# Potentiostat.net
KiCad netlist of a schematic drawn in EAGLE
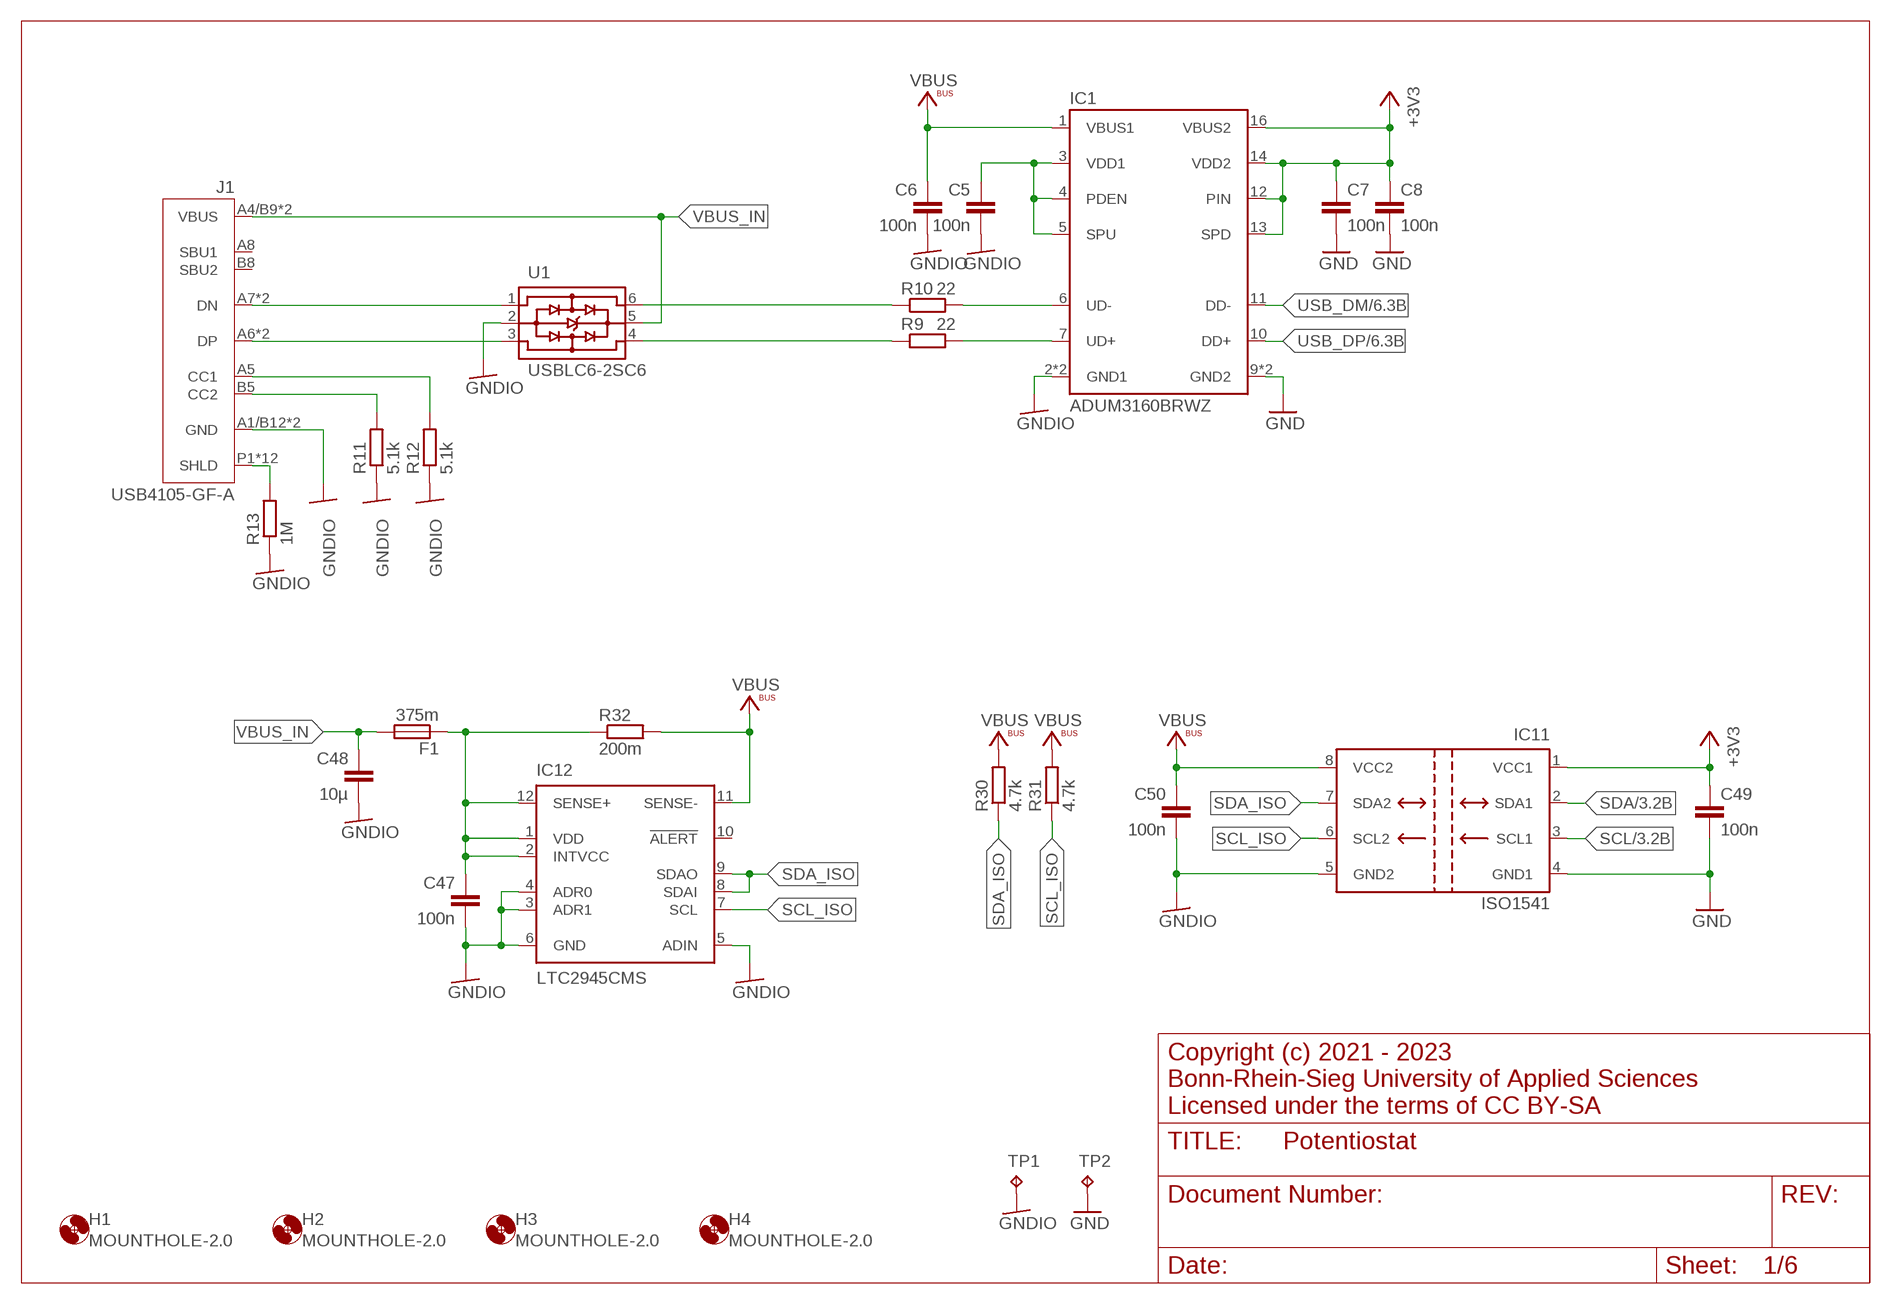
[diagram p0: schematic, sheet 1]
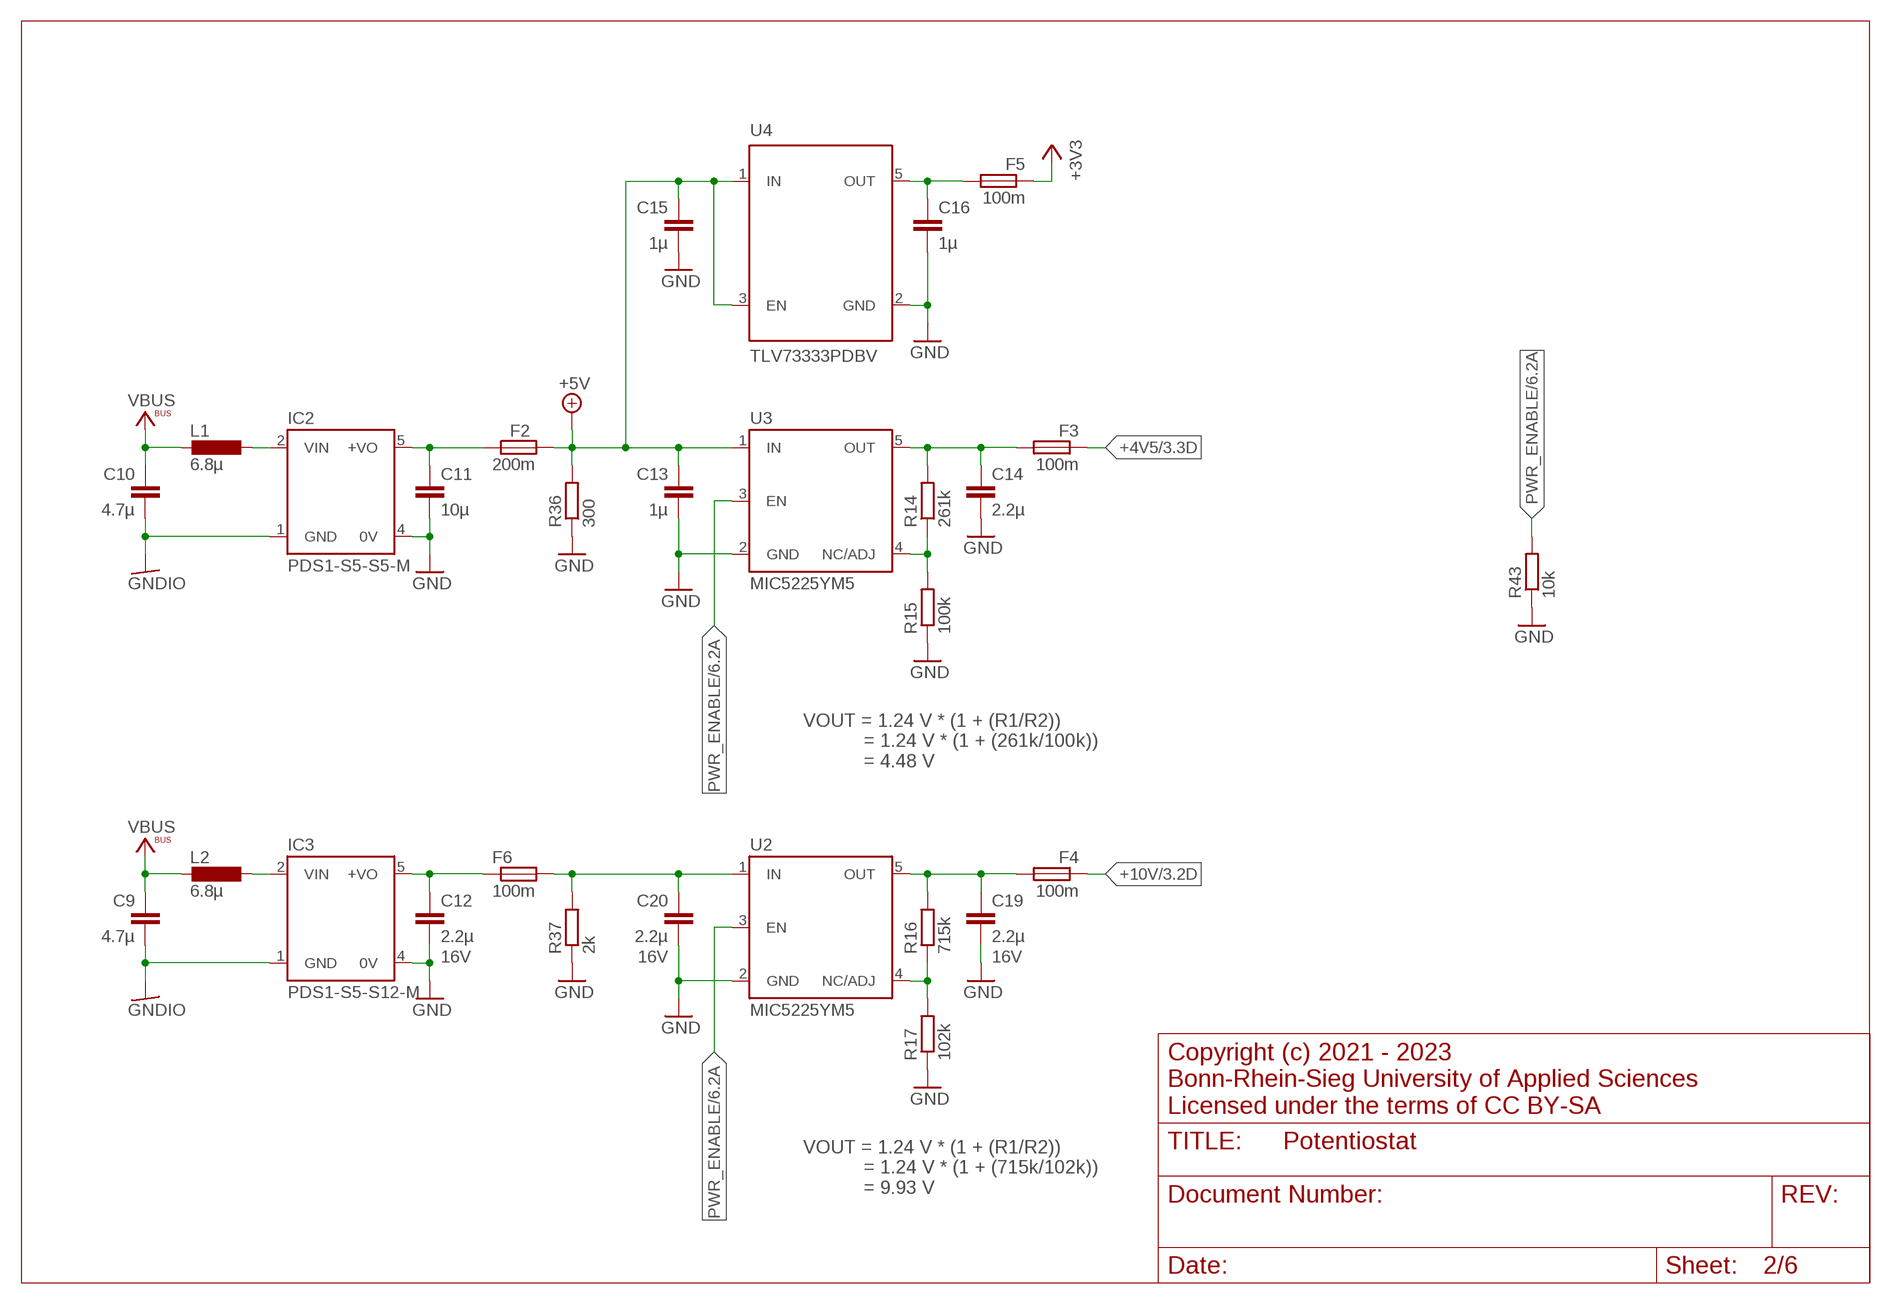
[diagram p1: schematic, sheet 2]
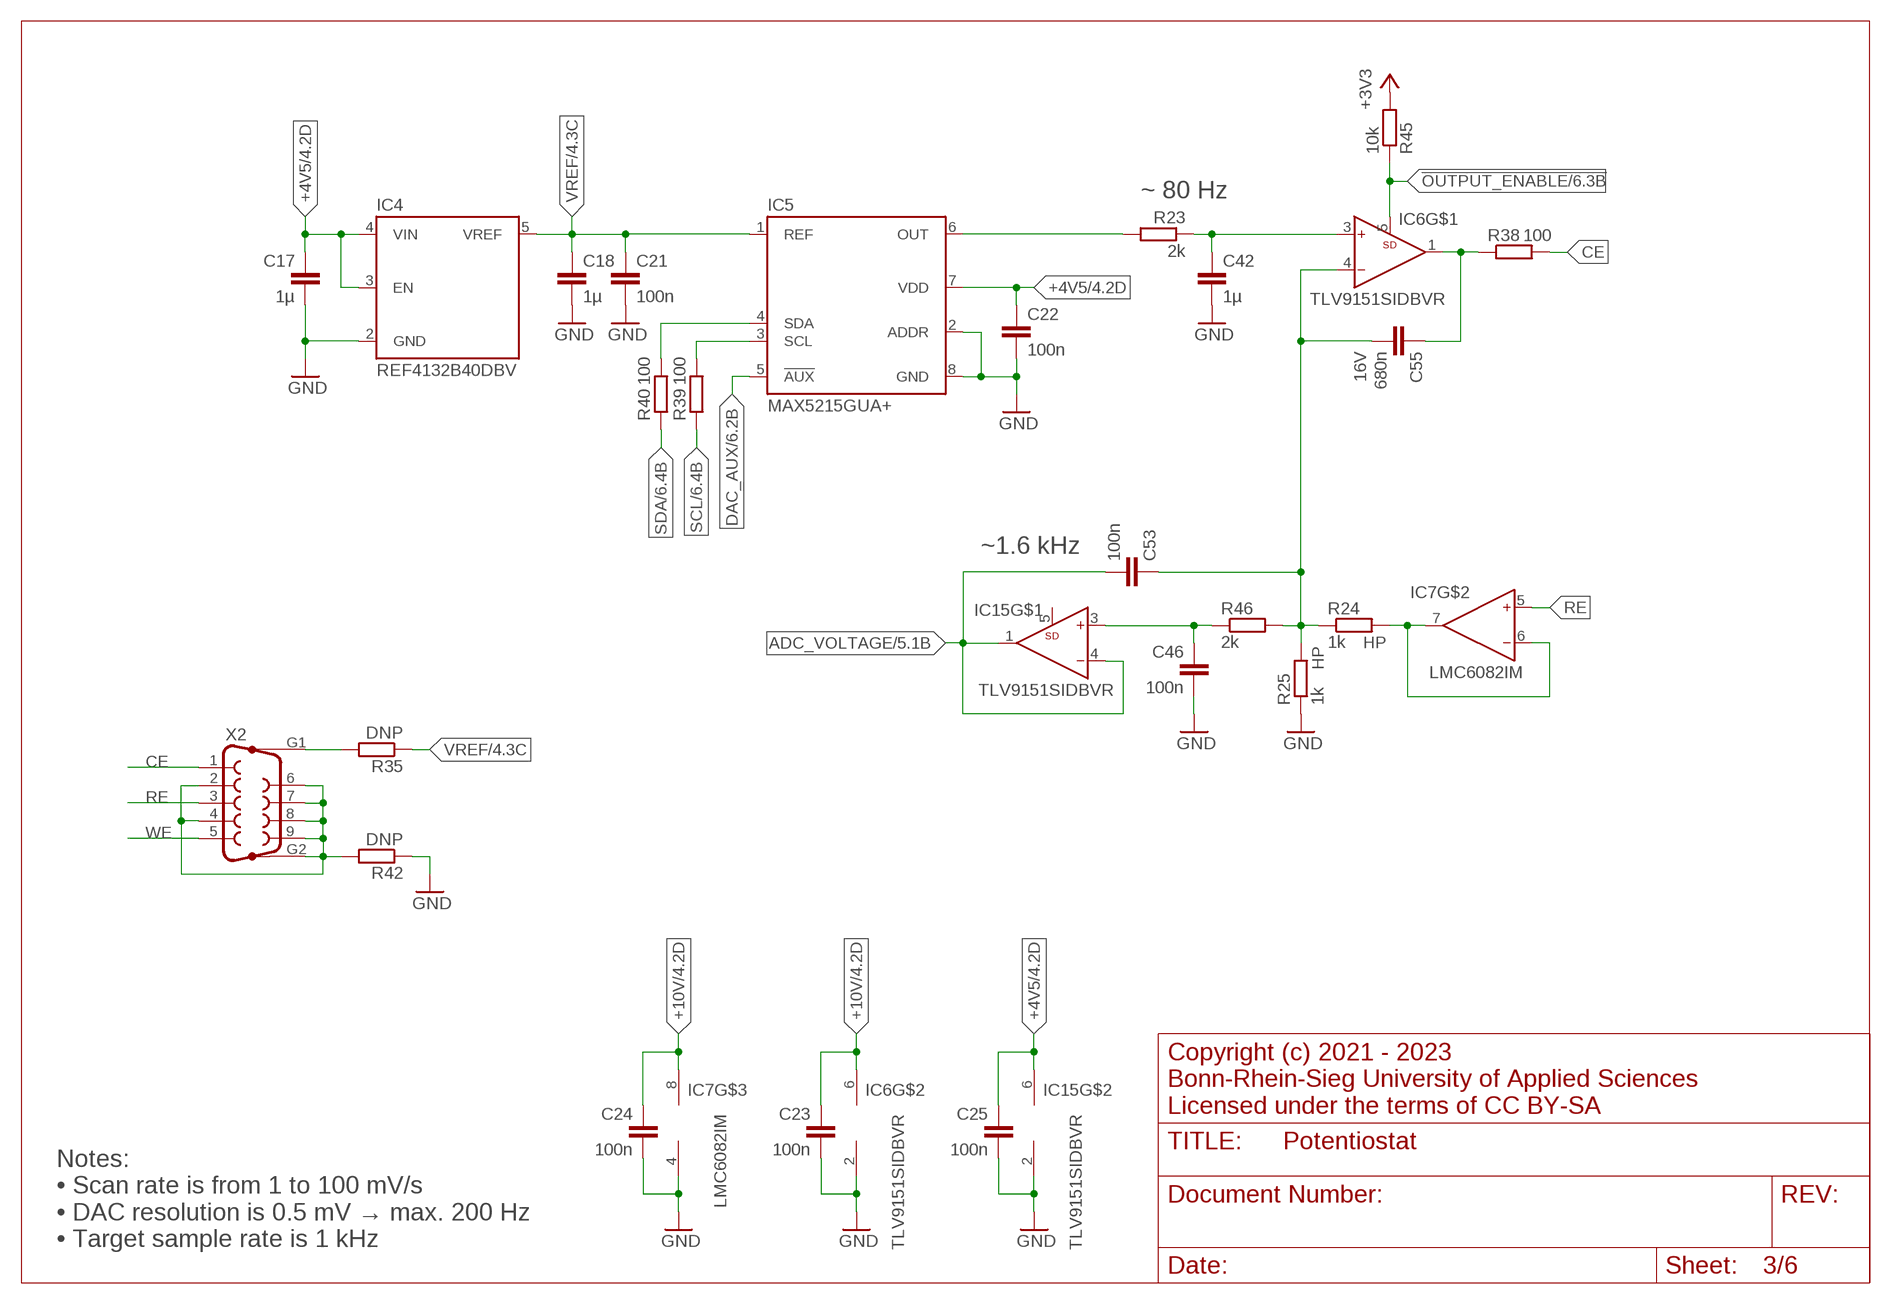
[diagram p2: schematic, sheet 3]
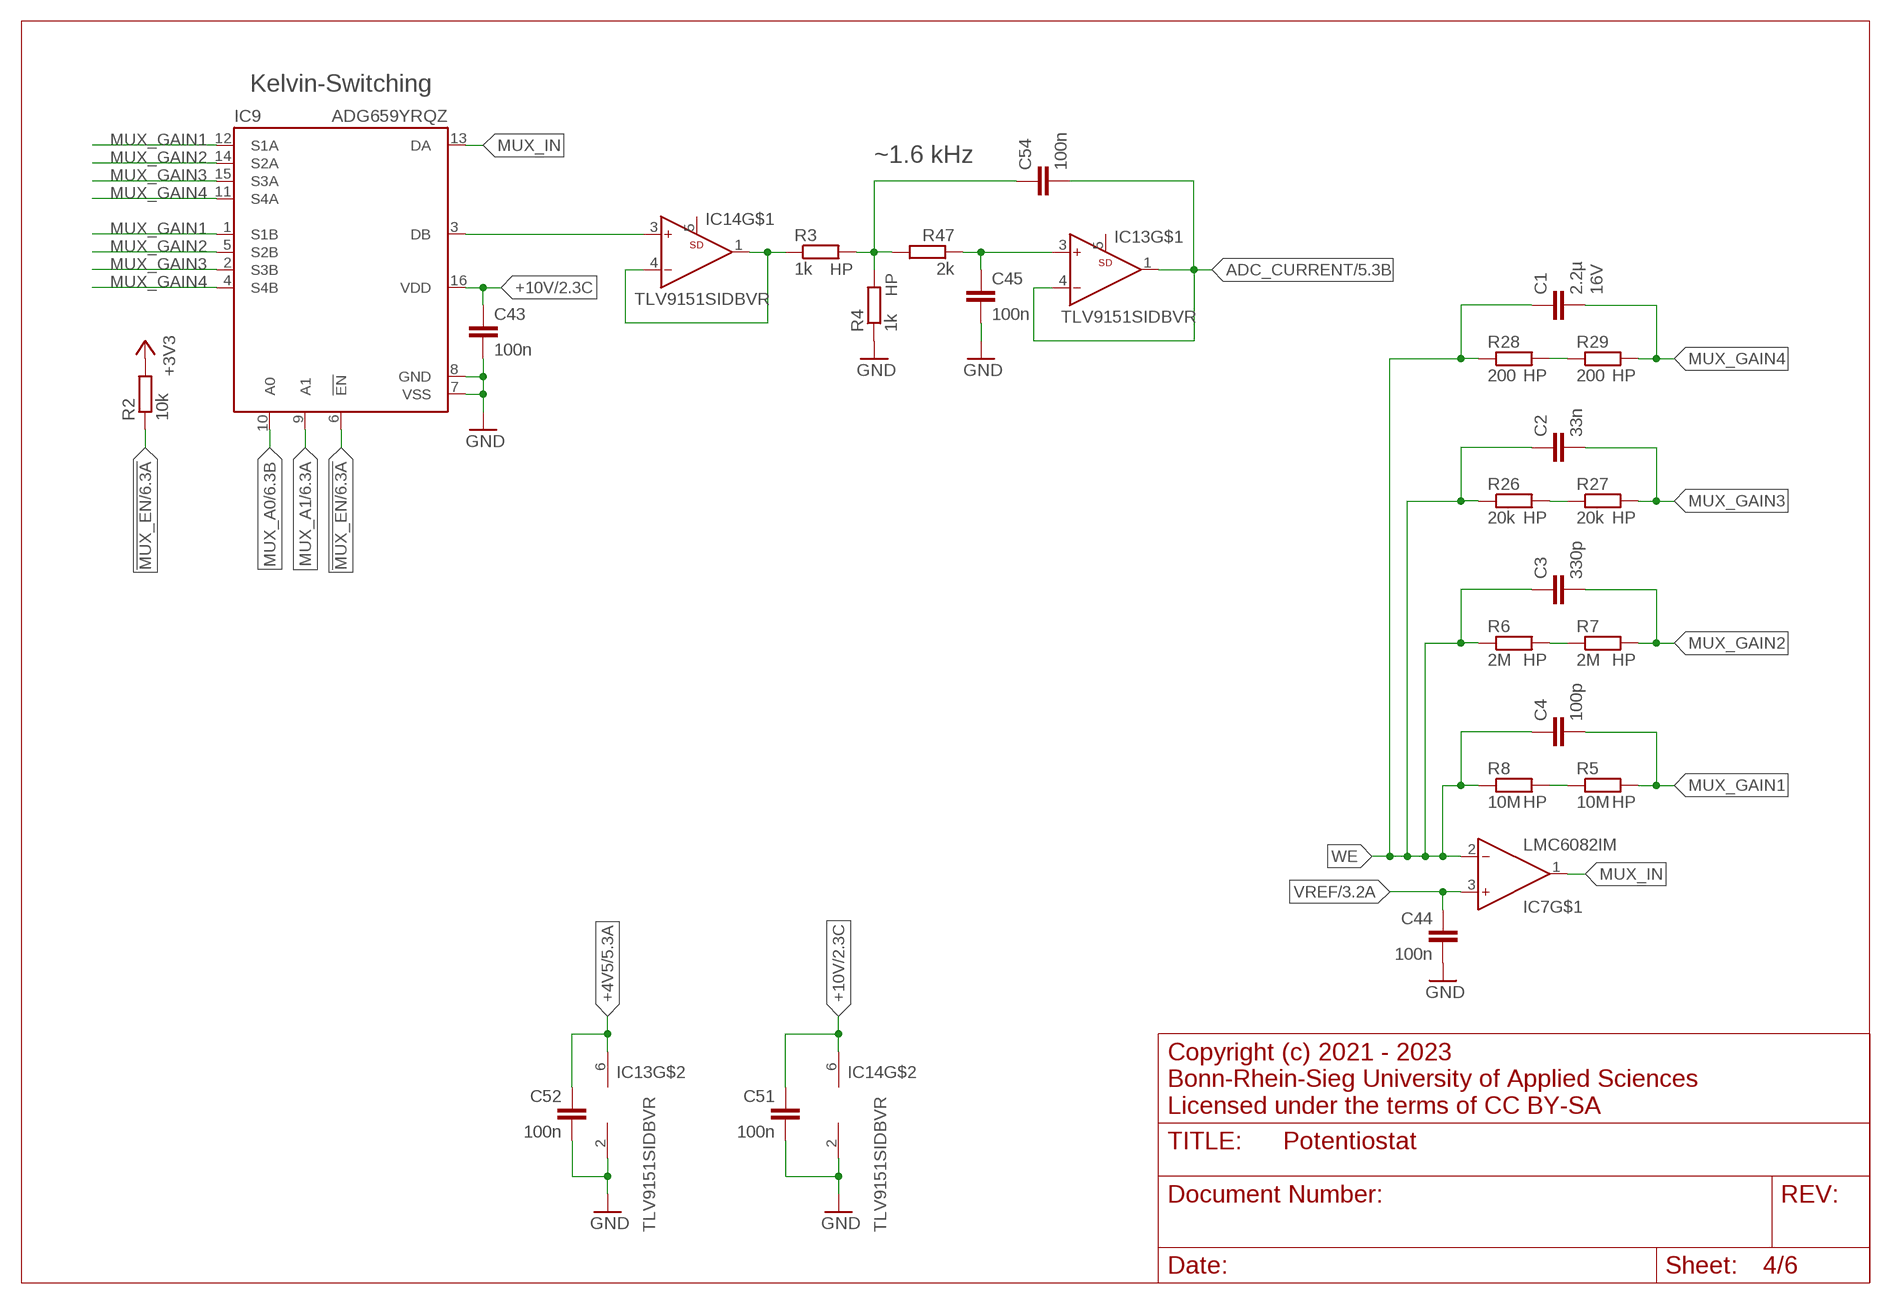
[diagram p3: schematic, sheet 4]
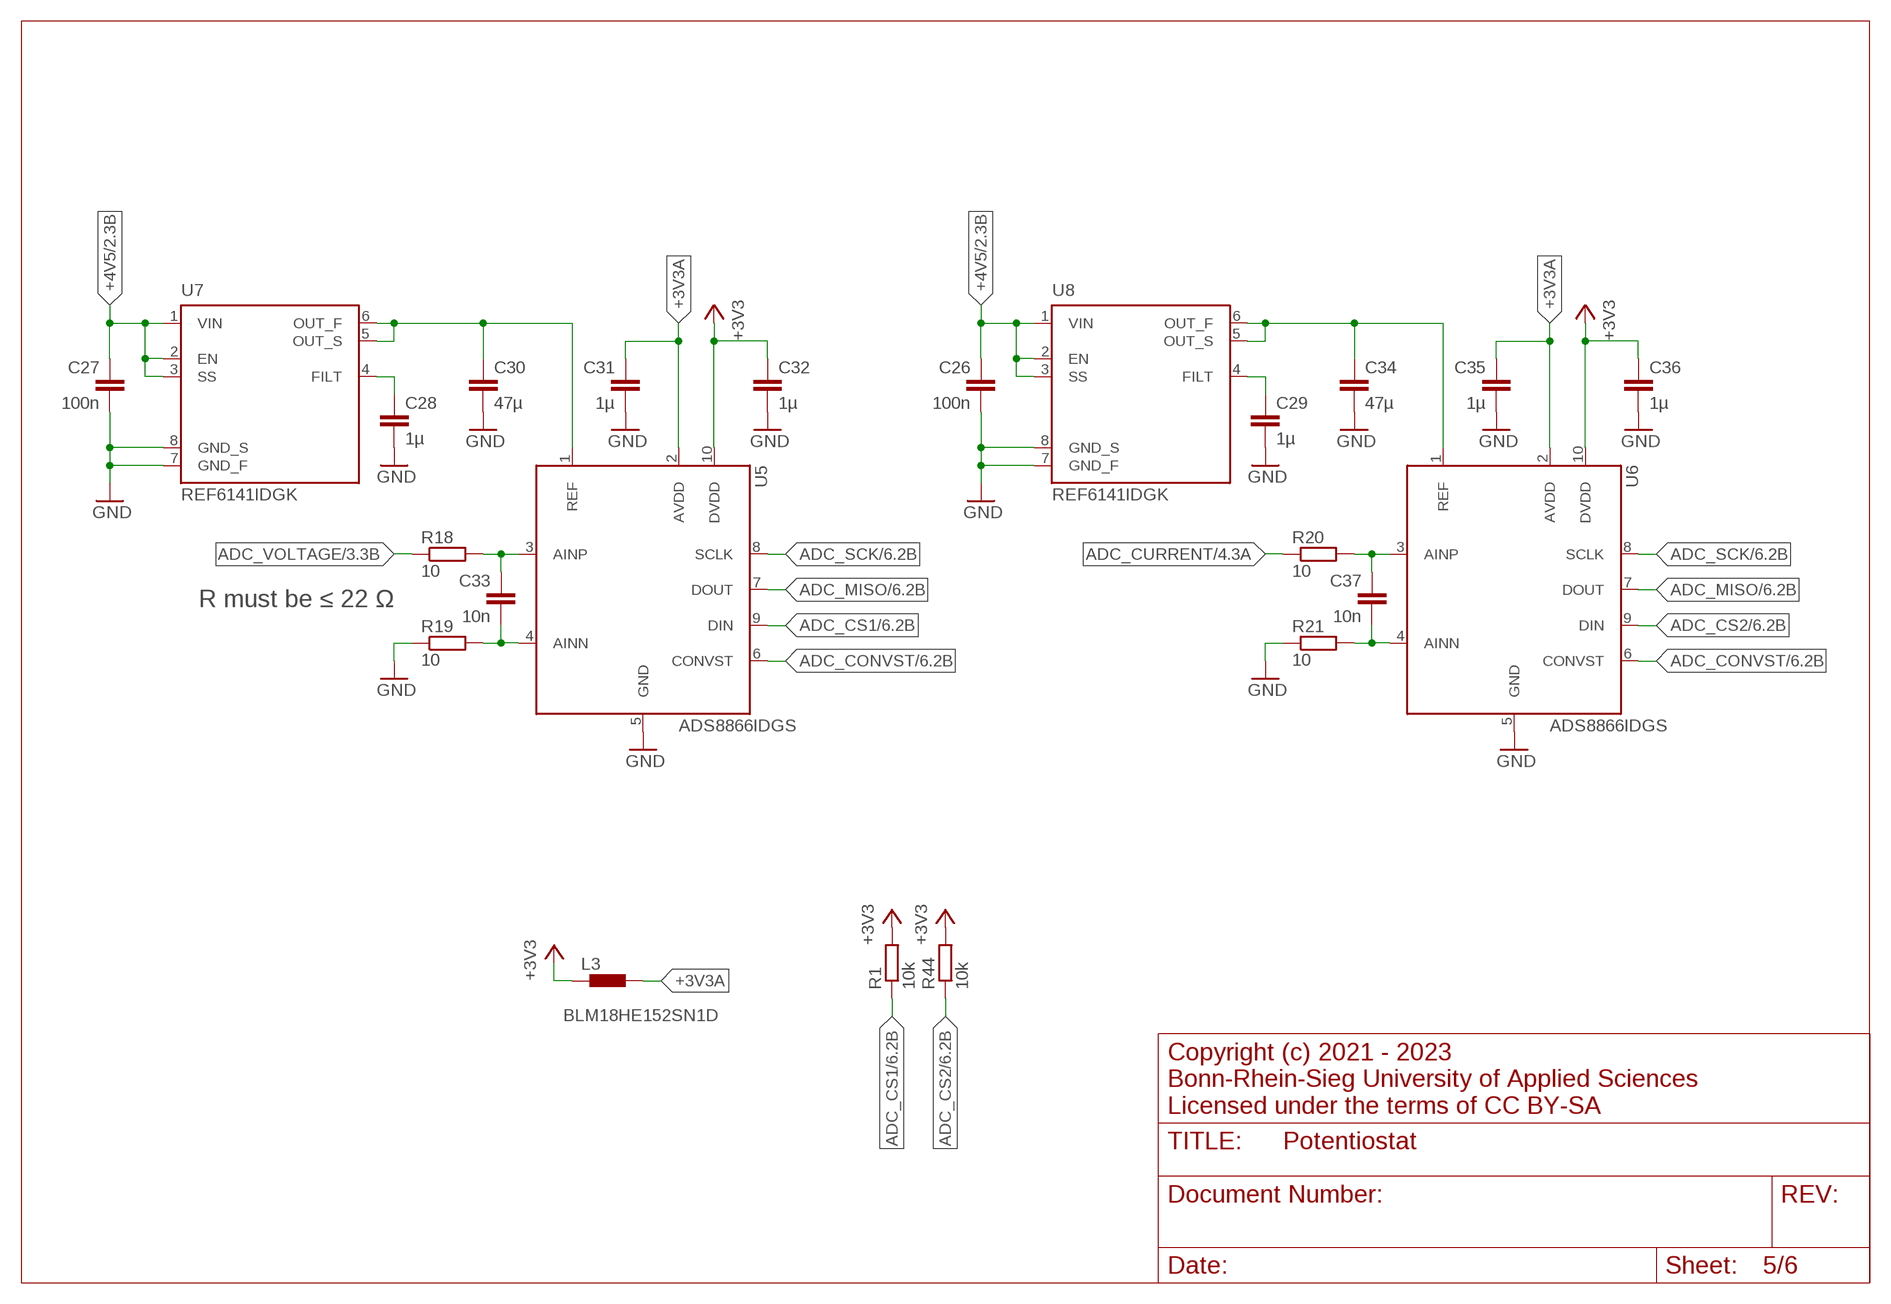
[diagram p4: schematic, sheet 5]
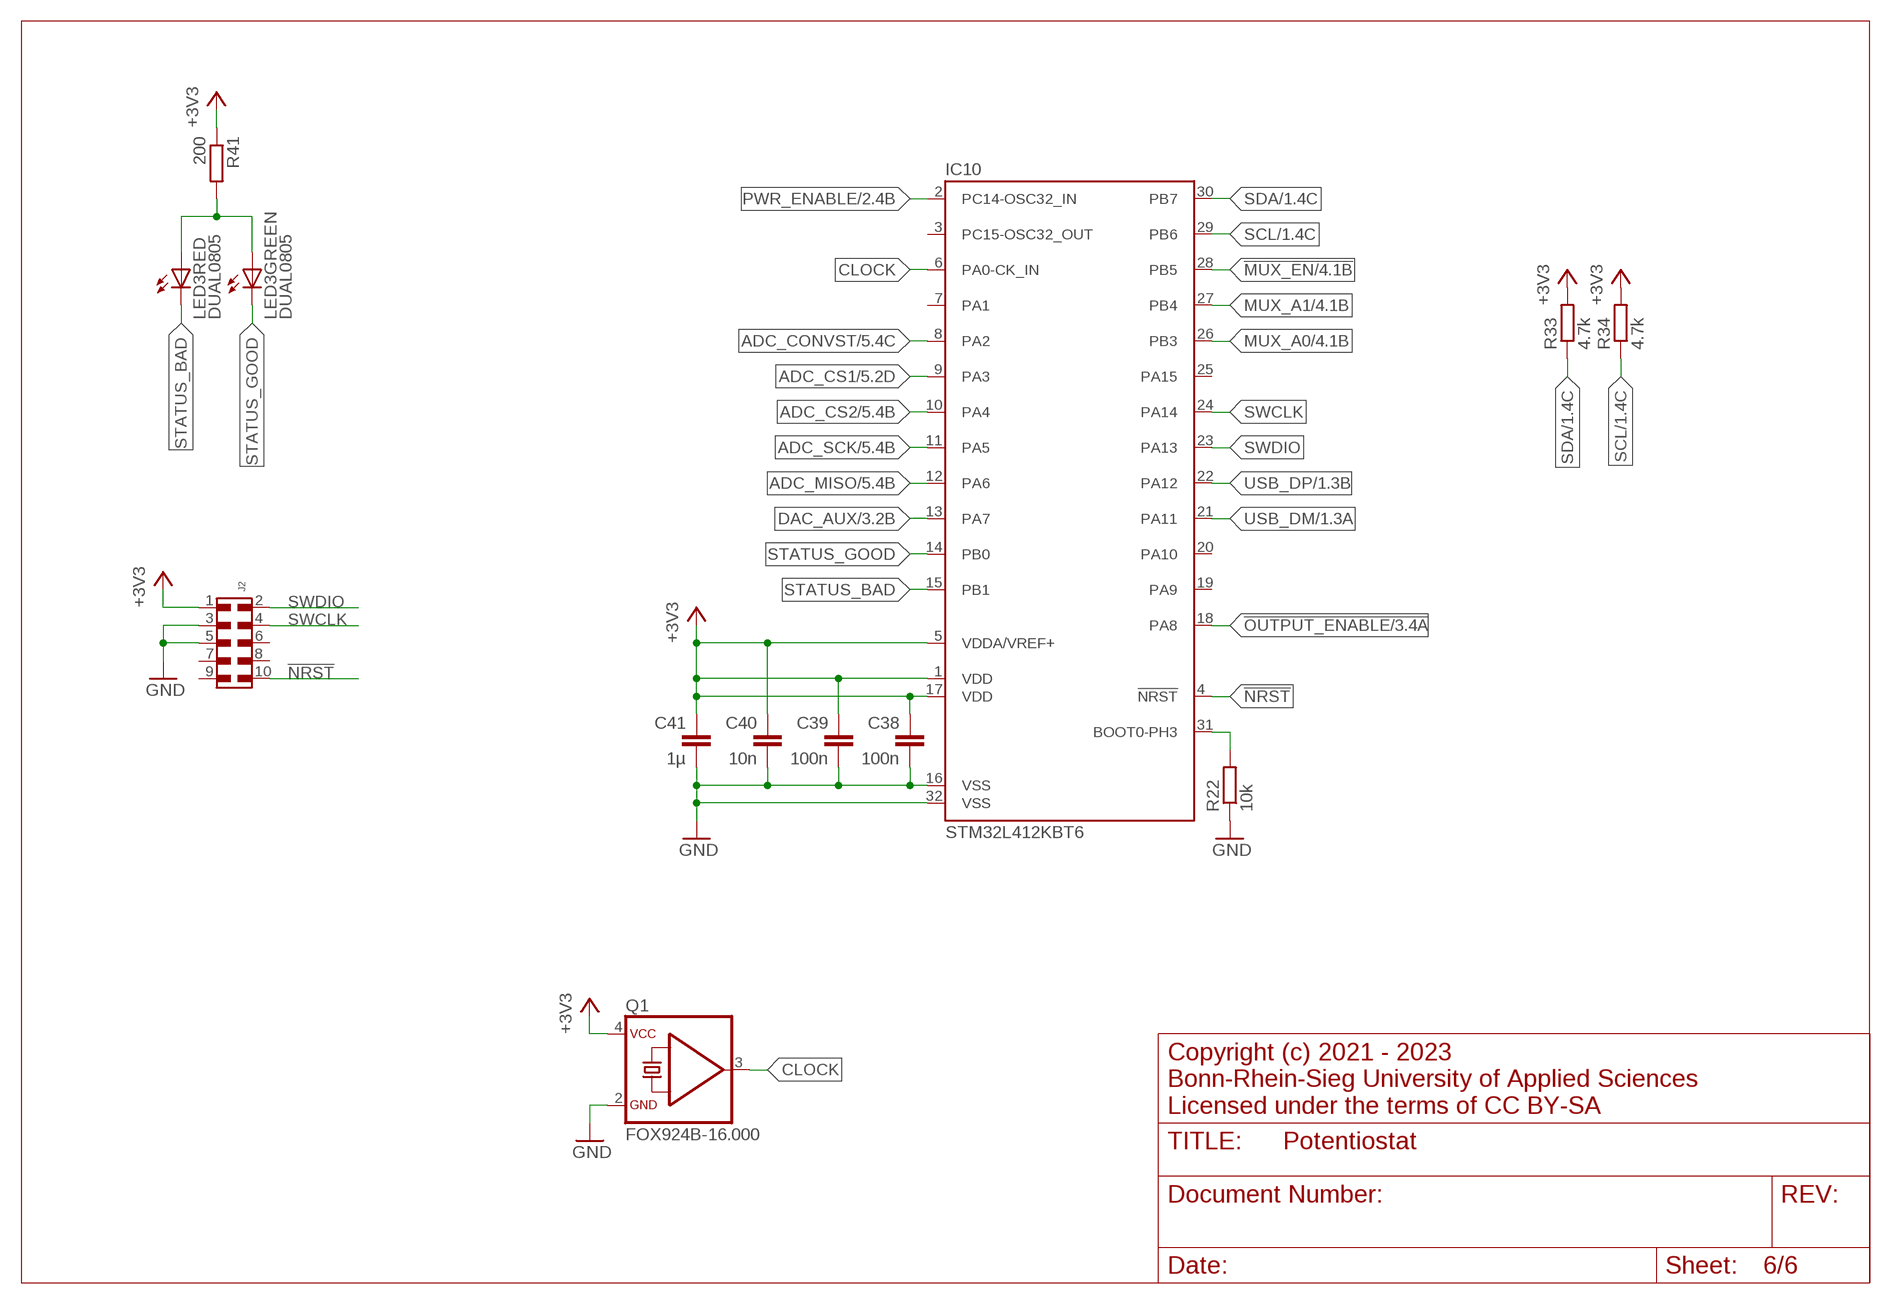
[diagram p5: schematic, sheet 6]

(export (version "E")
  (design (tool "Eeschema 10.0.6"))
  (components
    (comp (ref "C26")
      (value "100n")
      (footprint "eagle-import:C0603")
      (libsource (lib "eagle-import") (part "C-EUC0603"))
    )
    (comp (ref "C27")
      (value "100n")
      (footprint "eagle-import:C0603")
      (libsource (lib "eagle-import") (part "C-EUC0603"))
    )
    (comp (ref "C28")
      (value "1µ")
      (footprint "eagle-import:C0603")
      (libsource (lib "eagle-import") (part "C-EUC0603"))
    )
    (comp (ref "C29")
      (value "1µ")
      (footprint "eagle-import:C0603")
      (libsource (lib "eagle-import") (part "C-EUC0603"))
    )
    (comp (ref "C30")
      (value "47µ")
      (footprint "eagle-import:C0805")
      (libsource (lib "eagle-import") (part "C-EUC0805"))
    )
    (comp (ref "C31")
      (value "1µ")
      (footprint "eagle-import:C0603")
      (libsource (lib "eagle-import") (part "C-EUC0603"))
    )
    (comp (ref "C32")
      (value "1µ")
      (footprint "eagle-import:C0603")
      (libsource (lib "eagle-import") (part "C-EUC0603"))
    )
    (comp (ref "C33")
      (value "10n")
      (footprint "eagle-import:C0603")
      (libsource (lib "eagle-import") (part "C-EUC0603"))
    )
    (comp (ref "C34")
      (value "47µ")
      (footprint "eagle-import:C0805")
      (libsource (lib "eagle-import") (part "C-EUC0805"))
    )
    (comp (ref "C35")
      (value "1µ")
      (footprint "eagle-import:C0603")
      (libsource (lib "eagle-import") (part "C-EUC0603"))
    )
    (comp (ref "C36")
      (value "1µ")
      (footprint "eagle-import:C0603")
      (libsource (lib "eagle-import") (part "C-EUC0603"))
    )
    (comp (ref "C37")
      (value "10n")
      (footprint "eagle-import:C0603")
      (libsource (lib "eagle-import") (part "C-EUC0603"))
    )
    (comp (ref "L3")
      (value "BLM18HE152SN1D")
      (footprint "eagle-import:0603")
      (libsource (lib "eagle-import") (part "BLM18HE152SN1D"))
    )
    (comp (ref "R1")
      (value "10k")
      (footprint "eagle-import:R0603")
      (libsource (lib "eagle-import") (part "R-EU_R0603"))
    )
    (comp (ref "R18")
      (value "10")
      (footprint "eagle-import:R0603")
      (libsource (lib "eagle-import") (part "R-EU_R0603"))
    )
    (comp (ref "R19")
      (value "10")
      (footprint "eagle-import:R0603")
      (libsource (lib "eagle-import") (part "R-EU_R0603"))
    )
    (comp (ref "R20")
      (value "10")
      (footprint "eagle-import:R0603")
      (libsource (lib "eagle-import") (part "R-EU_R0603"))
    )
    (comp (ref "R21")
      (value "10")
      (footprint "eagle-import:R0603")
      (libsource (lib "eagle-import") (part "R-EU_R0603"))
    )
    (comp (ref "R44")
      (value "10k")
      (footprint "eagle-import:R0603")
      (libsource (lib "eagle-import") (part "R-EU_R0603"))
    )
    (comp (ref "U5")
      (value "ADS8866IDGS")
      (footprint "eagle-import:MSOP10")
      (libsource (lib "eagle-import") (part "ADS8866IDGS"))
    )
    (comp (ref "U6")
      (value "ADS8866IDGS")
      (footprint "eagle-import:MSOP10")
      (libsource (lib "eagle-import") (part "ADS8866IDGS"))
    )
    (comp (ref "U7")
      (value "REF6141IDGK")
      (footprint "eagle-import:VSSOP8")
      (libsource (lib "eagle-import") (part "REF61IDGK41"))
    )
    (comp (ref "U8")
      (value "REF6141IDGK")
      (footprint "eagle-import:VSSOP8")
      (libsource (lib "eagle-import") (part "REF61IDGK41"))
    )
    (comp (ref "C17")
      (value "1µ")
      (footprint "eagle-import:C0603")
      (libsource (lib "eagle-import") (part "C-EUC0603"))
    )
    (comp (ref "C18")
      (value "1µ")
      (footprint "eagle-import:C0603")
      (libsource (lib "eagle-import") (part "C-EUC0603"))
    )
    (comp (ref "C21")
      (value "100n")
      (footprint "eagle-import:C0603")
      (libsource (lib "eagle-import") (part "C-EUC0603"))
    )
    (comp (ref "C22")
      (value "100n")
      (footprint "eagle-import:C0603")
      (libsource (lib "eagle-import") (part "C-EUC0603"))
    )
    (comp (ref "C23")
      (value "100n")
      (footprint "eagle-import:C0603")
      (libsource (lib "eagle-import") (part "C-EUC0603"))
    )
    (comp (ref "C24")
      (value "100n")
      (footprint "eagle-import:C0603")
      (libsource (lib "eagle-import") (part "C-EUC0603"))
    )
    (comp (ref "C25")
      (value "100n")
      (footprint "eagle-import:C0603")
      (libsource (lib "eagle-import") (part "C-EUC0603"))
    )
    (comp (ref "C42")
      (value "1µ")
      (footprint "eagle-import:C0603")
      (libsource (lib "eagle-import") (part "C-EUC0603"))
    )
    (comp (ref "C46")
      (value "100n")
      (footprint "eagle-import:C0603")
      (libsource (lib "eagle-import") (part "C-EUC0603"))
    )
    (comp (ref "C53")
      (value "100n")
      (footprint "eagle-import:C0603")
      (libsource (lib "eagle-import") (part "C-EUC0603"))
    )
    (comp (ref "C55")
      (value "680n")
      (footprint "eagle-import:C0603")
      (fields (field (name "RATING") "16V"))
      (libsource (lib "eagle-import") (part "C-EUC0603"))
    )
    (comp (ref "IC4")
      (value "REF4132B40DBV")
      (footprint "eagle-import:SOT23-5")
      (libsource (lib "eagle-import") (part "REF4132DBVB40"))
    )
    (comp (ref "IC5")
      (value "MAX5215GUA+")
      (footprint "eagle-import:MSOP8")
      (libsource (lib "eagle-import") (part "MAX521GUA+5"))
    )
    (comp (ref "IC6")
      (value "TLV9151SIDBVR")
      (footprint "eagle-import:SOT23-6")
      (libsource (lib "eagle-import") (part "TLV9151SI?RDBV"))
    )
    (comp (ref "IC7")
      (value "LMC6082IM")
      (footprint "eagle-import:SOIC8")
      (libsource (lib "eagle-import") (part "LMC6082MI"))
    )
    (comp (ref "IC15")
      (value "TLV9151SIDBVR")
      (footprint "eagle-import:SOT23-6")
      (libsource (lib "eagle-import") (part "TLV9151SI?RDBV"))
    )
    (comp (ref "R23")
      (value "2k")
      (footprint "eagle-import:R0603")
      (libsource (lib "eagle-import") (part "R-EU_R0603"))
    )
    (comp (ref "R24")
      (value "1k")
      (footprint "eagle-import:R0603")
      (libsource (lib "eagle-import") (part "R-EU_R0603"))
    )
    (comp (ref "R25")
      (value "1k")
      (footprint "eagle-import:R0603")
      (libsource (lib "eagle-import") (part "R-EU_R0603"))
    )
    (comp (ref "R35")
      (value "DNP")
      (footprint "eagle-import:R0603")
      (libsource (lib "eagle-import") (part "R-EU_R0603"))
    )
    (comp (ref "R38")
      (value "100")
      (footprint "eagle-import:R0603")
      (libsource (lib "eagle-import") (part "R-EU_R0603"))
    )
    (comp (ref "R39")
      (value "100")
      (footprint "eagle-import:R0603")
      (libsource (lib "eagle-import") (part "R-EU_R0603"))
    )
    (comp (ref "R40")
      (value "100")
      (footprint "eagle-import:R0603")
      (libsource (lib "eagle-import") (part "R-EU_R0603"))
    )
    (comp (ref "R42")
      (value "DNP")
      (footprint "eagle-import:R0603")
      (libsource (lib "eagle-import") (part "R-EU_R0603"))
    )
    (comp (ref "R45")
      (value "10k")
      (footprint "eagle-import:R0603")
      (libsource (lib "eagle-import") (part "R-EU_R0603"))
    )
    (comp (ref "R46")
      (value "2k")
      (footprint "eagle-import:R0603")
      (libsource (lib "eagle-import") (part "R-EU_R0603"))
    )
    (comp (ref "X2")
      (value "A-DF_09")
      (footprint "eagle-import:A-DF_09")
      (libsource (lib "eagle-import") (part "A-DF_09"))
    )
    (comp (ref "C5")
      (value "100n")
      (footprint "eagle-import:C0603")
      (libsource (lib "eagle-import") (part "C-EUC0603"))
    )
    (comp (ref "C6")
      (value "100n")
      (footprint "eagle-import:C0603")
      (libsource (lib "eagle-import") (part "C-EUC0603"))
    )
    (comp (ref "C7")
      (value "100n")
      (footprint "eagle-import:C0603")
      (libsource (lib "eagle-import") (part "C-EUC0603"))
    )
    (comp (ref "C8")
      (value "100n")
      (footprint "eagle-import:C0603")
      (libsource (lib "eagle-import") (part "C-EUC0603"))
    )
    (comp (ref "C47")
      (value "100n")
      (footprint "eagle-import:C0603")
      (libsource (lib "eagle-import") (part "C-EUC0603"))
    )
    (comp (ref "C48")
      (value "10µ")
      (footprint "eagle-import:C0603")
      (libsource (lib "eagle-import") (part "C-EUC0603"))
    )
    (comp (ref "C49")
      (value "100n")
      (footprint "eagle-import:C0603")
      (libsource (lib "eagle-import") (part "C-EUC0603"))
    )
    (comp (ref "C50")
      (value "100n")
      (footprint "eagle-import:C0603")
      (libsource (lib "eagle-import") (part "C-EUC0603"))
    )
    (comp (ref "F1")
      (value "375m")
      (footprint "eagle-import:R0603")
      (libsource (lib "eagle-import") (part "FUSE0603"))
    )
    (comp (ref "H1")
      (value "MOUNTHOLE-2.0")
      (footprint "eagle-import:2.0")
      (libsource (lib "eagle-import") (part "MOUNTHOLE-2.0"))
    )
    (comp (ref "H2")
      (value "MOUNTHOLE-2.0")
      (footprint "eagle-import:2.0")
      (libsource (lib "eagle-import") (part "MOUNTHOLE-2.0"))
    )
    (comp (ref "H3")
      (value "MOUNTHOLE-2.0")
      (footprint "eagle-import:2.0")
      (libsource (lib "eagle-import") (part "MOUNTHOLE-2.0"))
    )
    (comp (ref "H4")
      (value "MOUNTHOLE-2.0")
      (footprint "eagle-import:2.0")
      (libsource (lib "eagle-import") (part "MOUNTHOLE-2.0"))
    )
    (comp (ref "IC1")
      (value "ADUM3160BRWZ")
      (footprint "eagle-import:SO16W")
      (libsource (lib "eagle-import") (part "ADUM3160BRWZ"))
    )
    (comp (ref "IC11")
      (value "ISO1541")
      (footprint "eagle-import:SOIC8")
      (libsource (lib "eagle-import") (part "ISO1541"))
    )
    (comp (ref "IC12")
      (value "LTC2945CMS")
      (footprint "eagle-import:MSOP12")
      (libsource (lib "eagle-import") (part "LTC2945MSC"))
    )
    (comp (ref "J1")
      (value "USB4105-GF-A")
      (footprint "eagle-import:USB4105-GF-A")
      (libsource (lib "eagle-import") (part "USB4105-GF-A"))
    )
    (comp (ref "R9")
      (value "22")
      (footprint "eagle-import:R0603")
      (libsource (lib "eagle-import") (part "R-EU_R0603"))
    )
    (comp (ref "R10")
      (value "22")
      (footprint "eagle-import:R0603")
      (libsource (lib "eagle-import") (part "R-EU_R0603"))
    )
    (comp (ref "R11")
      (value "5.1k")
      (footprint "eagle-import:R0603")
      (libsource (lib "eagle-import") (part "R-EU_R0603"))
    )
    (comp (ref "R12")
      (value "5.1k")
      (footprint "eagle-import:R0603")
      (libsource (lib "eagle-import") (part "R-EU_R0603"))
    )
    (comp (ref "R13")
      (value "1M")
      (footprint "eagle-import:R0603")
      (libsource (lib "eagle-import") (part "R-EU_R0603"))
    )
    (comp (ref "R30")
      (value "4.7k")
      (footprint "eagle-import:R0603")
      (libsource (lib "eagle-import") (part "R-EU_R0603"))
    )
    (comp (ref "R31")
      (value "4.7k")
      (footprint "eagle-import:R0603")
      (libsource (lib "eagle-import") (part "R-EU_R0603"))
    )
    (comp (ref "R32")
      (value "200m")
      (footprint "eagle-import:R0805")
      (libsource (lib "eagle-import") (part "R-EU_R0805"))
    )
    (comp (ref "TP1")
      (value "TP3.8X2.03")
      (footprint "eagle-import:3.8X2.03")
      (libsource (lib "eagle-import") (part "TP3.8X2.03"))
    )
    (comp (ref "TP2")
      (value "TP3.8X2.03")
      (footprint "eagle-import:3.8X2.03")
      (libsource (lib "eagle-import") (part "TP3.8X2.03"))
    )
    (comp (ref "U1")
      (value "USBLC6-2SC6")
      (footprint "eagle-import:SOT23-6L")
      (libsource (lib "eagle-import") (part "USBLC6-2SC6"))
    )
    (comp (ref "C38")
      (value "100n")
      (footprint "eagle-import:C0603")
      (libsource (lib "eagle-import") (part "C-EUC0603"))
    )
    (comp (ref "C39")
      (value "100n")
      (footprint "eagle-import:C0603")
      (libsource (lib "eagle-import") (part "C-EUC0603"))
    )
    (comp (ref "C40")
      (value "10n")
      (footprint "eagle-import:C0603")
      (libsource (lib "eagle-import") (part "C-EUC0603"))
    )
    (comp (ref "C41")
      (value "1µ")
      (footprint "eagle-import:C0603")
      (libsource (lib "eagle-import") (part "C-EUC0603"))
    )
    (comp (ref "IC10")
      (value "STM32L412KBT6")
      (footprint "eagle-import:LQFP32")
      (libsource (lib "eagle-import") (part "STM32L412K?T6B"))
    )
    (comp (ref "J2")
      (value "6210XX21021_62101021021")
      (footprint "eagle-import:62101021021")
      (libsource (lib "eagle-import") (part "6210XX21021_62101021021"))
    )
    (comp (ref "LED3")
      (value "DUAL0805")
      (footprint "eagle-import:CHIPLEDX2")
      (libsource (lib "eagle-import") (part "DUAL0805"))
    )
    (comp (ref "Q1")
      (value "FOX924B-16.000")
      (footprint "eagle-import:FOX924B")
      (libsource (lib "eagle-import") (part "FOX924B-16.000"))
    )
    (comp (ref "R22")
      (value "10k")
      (footprint "eagle-import:R0603")
      (libsource (lib "eagle-import") (part "rcl_334_R-EU_R0603"))
    )
    (comp (ref "R33")
      (value "4.7k")
      (footprint "eagle-import:R0603")
      (libsource (lib "eagle-import") (part "R-EU_R0603"))
    )
    (comp (ref "R34")
      (value "4.7k")
      (footprint "eagle-import:R0603")
      (libsource (lib "eagle-import") (part "R-EU_R0603"))
    )
    (comp (ref "R41")
      (value "200")
      (footprint "eagle-import:R0603")
      (libsource (lib "eagle-import") (part "rcl_334_R-EU_R0603"))
    )
    (comp (ref "C1")
      (value "2.2µ")
      (footprint "eagle-import:C0603")
      (fields (field (name "RATING") "16V"))
      (libsource (lib "eagle-import") (part "C-EUC0603"))
    )
    (comp (ref "C2")
      (value "33n")
      (footprint "eagle-import:C0603")
      (libsource (lib "eagle-import") (part "C-EUC0603"))
    )
    (comp (ref "C3")
      (value "330p")
      (footprint "eagle-import:C0603")
      (libsource (lib "eagle-import") (part "C-EUC0603"))
    )
    (comp (ref "C4")
      (value "100p")
      (footprint "eagle-import:C0603")
      (libsource (lib "eagle-import") (part "C-EUC0603"))
    )
    (comp (ref "C43")
      (value "100n")
      (footprint "eagle-import:C0603")
      (libsource (lib "eagle-import") (part "C-EUC0603"))
    )
    (comp (ref "C44")
      (value "100n")
      (footprint "eagle-import:C0603")
      (libsource (lib "eagle-import") (part "C-EUC0603"))
    )
    (comp (ref "C45")
      (value "100n")
      (footprint "eagle-import:C0603")
      (libsource (lib "eagle-import") (part "C-EUC0603"))
    )
    (comp (ref "C51")
      (value "100n")
      (footprint "eagle-import:C0603")
      (libsource (lib "eagle-import") (part "C-EUC0603"))
    )
    (comp (ref "C52")
      (value "100n")
      (footprint "eagle-import:C0603")
      (libsource (lib "eagle-import") (part "C-EUC0603"))
    )
    (comp (ref "C54")
      (value "100n")
      (footprint "eagle-import:C0603")
      (libsource (lib "eagle-import") (part "C-EUC0603"))
    )
    (comp (ref "IC9")
      (value "ADG659YRQZ")
      (footprint "eagle-import:QSOP16")
      (libsource (lib "eagle-import") (part "ADG659YRQZ"))
    )
    (comp (ref "IC13")
      (value "TLV9151SIDBVR")
      (footprint "eagle-import:SOT23-6")
      (libsource (lib "eagle-import") (part "TLV9151SI?RDBV"))
    )
    (comp (ref "IC14")
      (value "TLV9151SIDBVR")
      (footprint "eagle-import:SOT23-6")
      (libsource (lib "eagle-import") (part "TLV9151SI?RDBV"))
    )
    (comp (ref "R2")
      (value "10k")
      (footprint "eagle-import:R0603")
      (libsource (lib "eagle-import") (part "R-EU_R0603"))
    )
    (comp (ref "R3")
      (value "1k")
      (footprint "eagle-import:R0603")
      (libsource (lib "eagle-import") (part "R-EU_R0603"))
    )
    (comp (ref "R4")
      (value "1k")
      (footprint "eagle-import:R0603")
      (libsource (lib "eagle-import") (part "R-EU_R0603"))
    )
    (comp (ref "R5")
      (value "10M")
      (footprint "eagle-import:R0805")
      (libsource (lib "eagle-import") (part "R-EU_R0805"))
    )
    (comp (ref "R6")
      (value "2M")
      (footprint "eagle-import:R0805")
      (libsource (lib "eagle-import") (part "R-EU_R0805"))
    )
    (comp (ref "R7")
      (value "2M")
      (footprint "eagle-import:R0805")
      (libsource (lib "eagle-import") (part "R-EU_R0805"))
    )
    (comp (ref "R8")
      (value "10M")
      (footprint "eagle-import:R0805")
      (libsource (lib "eagle-import") (part "R-EU_R0805"))
    )
    (comp (ref "R26")
      (value "20k")
      (footprint "eagle-import:R0805")
      (libsource (lib "eagle-import") (part "R-EU_R0805"))
    )
    (comp (ref "R27")
      (value "20k")
      (footprint "eagle-import:R0805")
      (libsource (lib "eagle-import") (part "R-EU_R0805"))
    )
    (comp (ref "R28")
      (value "200")
      (footprint "eagle-import:R0805")
      (libsource (lib "eagle-import") (part "R-EU_R0805"))
    )
    (comp (ref "R29")
      (value "200")
      (footprint "eagle-import:R0805")
      (libsource (lib "eagle-import") (part "R-EU_R0805"))
    )
    (comp (ref "R47")
      (value "2k")
      (footprint "eagle-import:R0603")
      (libsource (lib "eagle-import") (part "R-EU_R0603"))
    )
    (comp (ref "C9")
      (value "4.7µ")
      (footprint "eagle-import:C0603")
      (libsource (lib "eagle-import") (part "C-EUC0603"))
    )
    (comp (ref "C10")
      (value "4.7µ")
      (footprint "eagle-import:C0603")
      (libsource (lib "eagle-import") (part "C-EUC0603"))
    )
    (comp (ref "C11")
      (value "10µ")
      (footprint "eagle-import:C0603")
      (libsource (lib "eagle-import") (part "C-EUC0603"))
    )
    (comp (ref "C12")
      (value "2.2µ")
      (footprint "eagle-import:C0603")
      (fields (field (name "RATING") "16V"))
      (libsource (lib "eagle-import") (part "C-EUC0603"))
    )
    (comp (ref "C13")
      (value "1µ")
      (footprint "eagle-import:C0603")
      (libsource (lib "eagle-import") (part "C-EUC0603"))
    )
    (comp (ref "C14")
      (value "2.2µ")
      (footprint "eagle-import:C0603")
      (libsource (lib "eagle-import") (part "C-EUC0603"))
    )
    (comp (ref "C15")
      (value "1µ")
      (footprint "eagle-import:C0603")
      (libsource (lib "eagle-import") (part "C-EUC0603"))
    )
    (comp (ref "C16")
      (value "1µ")
      (footprint "eagle-import:C0603")
      (libsource (lib "eagle-import") (part "C-EUC0603"))
    )
    (comp (ref "C19")
      (value "2.2µ")
      (footprint "eagle-import:C0603")
      (fields (field (name "RATING") "16V"))
      (libsource (lib "eagle-import") (part "C-EUC0603"))
    )
    (comp (ref "C20")
      (value "2.2µ")
      (footprint "eagle-import:C0603")
      (fields (field (name "RATING") "16V"))
      (libsource (lib "eagle-import") (part "C-EUC0603"))
    )
    (comp (ref "F2")
      (value "200m")
      (footprint "eagle-import:R0603")
      (libsource (lib "eagle-import") (part "FUSE0603"))
    )
    (comp (ref "F3")
      (value "100m")
      (footprint "eagle-import:R0603")
      (libsource (lib "eagle-import") (part "FUSE0603"))
    )
    (comp (ref "F4")
      (value "100m")
      (footprint "eagle-import:R0603")
      (libsource (lib "eagle-import") (part "FUSE0603"))
    )
    (comp (ref "F5")
      (value "100m")
      (footprint "eagle-import:R0603")
      (libsource (lib "eagle-import") (part "FUSE0603"))
    )
    (comp (ref "F6")
      (value "100m")
      (footprint "eagle-import:R0603")
      (libsource (lib "eagle-import") (part "FUSE0603"))
    )
    (comp (ref "IC2")
      (value "PDS1-S5-S5-M")
      (footprint "eagle-import:PDS1-M")
      (libsource (lib "eagle-import") (part "PDS1-S?-S-M55"))
    )
    (comp (ref "IC3")
      (value "PDS1-S5-S12-M")
      (footprint "eagle-import:PDS1-M")
      (libsource (lib "eagle-import") (part "PDS1-S?-S-M512"))
    )
    (comp (ref "L1")
      (value "6.8µ")
      (footprint "eagle-import:L0603")
      (libsource (lib "eagle-import") (part "L-EUL0603"))
    )
    (comp (ref "L2")
      (value "6.8µ")
      (footprint "eagle-import:L0603")
      (libsource (lib "eagle-import") (part "L-EUL0603"))
    )
    (comp (ref "R14")
      (value "261k")
      (footprint "eagle-import:R0603")
      (libsource (lib "eagle-import") (part "R-EU_R0603"))
    )
    (comp (ref "R15")
      (value "100k")
      (footprint "eagle-import:R0603")
      (libsource (lib "eagle-import") (part "R-EU_R0603"))
    )
    (comp (ref "R16")
      (value "715k")
      (footprint "eagle-import:R0603")
      (libsource (lib "eagle-import") (part "R-EU_R0603"))
    )
    (comp (ref "R17")
      (value "102k")
      (footprint "eagle-import:R0603")
      (libsource (lib "eagle-import") (part "R-EU_R0603"))
    )
    (comp (ref "R36")
      (value "300")
      (footprint "eagle-import:R0805")
      (libsource (lib "eagle-import") (part "R-EU_R0805"))
    )
    (comp (ref "R37")
      (value "2k")
      (footprint "eagle-import:R0805")
      (libsource (lib "eagle-import") (part "R-EU_R0805"))
    )
    (comp (ref "R43")
      (value "10k")
      (footprint "eagle-import:R0603")
      (libsource (lib "eagle-import") (part "R-EU_R0603"))
    )
    (comp (ref "U2")
      (value "MIC5225YM5")
      (footprint "eagle-import:SOT23-5L")
      (libsource (lib "eagle-import") (part "MIC5225YM5"))
    )
    (comp (ref "U3")
      (value "MIC5225YM5")
      (footprint "eagle-import:SOT23-5L")
      (libsource (lib "eagle-import") (part "MIC5225YM5"))
    )
    (comp (ref "U4")
      (value "TLV73333PDBV")
      (footprint "eagle-import:SOT-23")
      (libsource (lib "eagle-import") (part "TLV733P?DBV33"))
    )
  )
  (nets
    (net (code "1") (name "+3V3") (class "Default")
      (node (ref "C32") (pin "1") (pinfunction "1_1") (pintype "passive"))
      (node (ref "C36") (pin "1") (pinfunction "1_1") (pintype "passive"))
      (node (ref "C38") (pin "1") (pinfunction "1_1") (pintype "passive"))
      (node (ref "C39") (pin "1") (pinfunction "1_1") (pintype "passive"))
      (node (ref "C40") (pin "1") (pinfunction "1_1") (pintype "passive"))
      (node (ref "C41") (pin "1") (pinfunction "1_1") (pintype "passive"))
      (node (ref "C49") (pin "1") (pinfunction "1_1") (pintype "passive"))
      (node (ref "C7") (pin "1") (pinfunction "1_1") (pintype "passive"))
      (node (ref "C8") (pin "1") (pinfunction "1_1") (pintype "passive"))
      (node (ref "F5") (pin "1") (pinfunction "1_1") (pintype "passive"))
      (node (ref "IC1") (pin "12") (pinfunction "PIN_12") (pintype "bidirectional"))
      (node (ref "IC1") (pin "13") (pinfunction "SPD_13") (pintype "bidirectional"))
      (node (ref "IC1") (pin "14") (pinfunction "VDD2_14") (pintype "bidirectional"))
      (node (ref "IC1") (pin "16") (pinfunction "VBUS2_16") (pintype "bidirectional"))
      (node (ref "IC10") (pin "1") (pinfunction "VDD_1") (pintype "bidirectional"))
      (node (ref "IC10") (pin "17") (pinfunction "VDD_17") (pintype "bidirectional"))
      (node (ref "IC10") (pin "5") (pinfunction "VDDA/VREF+_5") (pintype "bidirectional"))
      (node (ref "IC11") (pin "1") (pinfunction "VCC1_1") (pintype "bidirectional"))
      (node (ref "J2") (pin "1") (pinfunction "1_1") (pintype "passive"))
      (node (ref "L3") (pin "2") (pinfunction "2_2") (pintype "passive"))
      (node (ref "Q1") (pin "4") (pinfunction "VCC_4") (pintype "power_in"))
      (node (ref "R1") (pin "2") (pinfunction "2_2") (pintype "passive"))
      (node (ref "R2") (pin "2") (pinfunction "2_2") (pintype "passive"))
      (node (ref "R33") (pin "2") (pinfunction "2_2") (pintype "passive"))
      (node (ref "R34") (pin "2") (pinfunction "2_2") (pintype "passive"))
      (node (ref "R41") (pin "1") (pinfunction "1_1") (pintype "passive"))
      (node (ref "R44") (pin "2") (pinfunction "2_2") (pintype "passive"))
      (node (ref "R45") (pin "2") (pinfunction "2_2") (pintype "passive"))
      (node (ref "U5") (pin "10") (pinfunction "DVDD_10") (pintype "bidirectional"))
      (node (ref "U6") (pin "10") (pinfunction "DVDD_10") (pintype "bidirectional"))
    )
    (net (code "2") (name "+3V3A") (class "Default")
      (node (ref "C31") (pin "1") (pinfunction "1_1") (pintype "passive"))
      (node (ref "C35") (pin "1") (pinfunction "1_1") (pintype "passive"))
      (node (ref "L3") (pin "1") (pinfunction "1_1") (pintype "passive"))
      (node (ref "U5") (pin "2") (pinfunction "AVDD_2") (pintype "bidirectional"))
      (node (ref "U6") (pin "2") (pinfunction "AVDD_2") (pintype "bidirectional"))
    )
    (net (code "3") (name "+4V5") (class "Default")
      (node (ref "C17") (pin "1") (pinfunction "1_1") (pintype "passive"))
      (node (ref "C22") (pin "1") (pinfunction "1_1") (pintype "passive"))
      (node (ref "C25") (pin "1") (pinfunction "1_1") (pintype "passive"))
      (node (ref "C26") (pin "1") (pinfunction "1_1") (pintype "passive"))
      (node (ref "C27") (pin "1") (pinfunction "1_1") (pintype "passive"))
      (node (ref "C52") (pin "1") (pinfunction "1_1") (pintype "passive"))
      (node (ref "F3") (pin "1") (pinfunction "1_1") (pintype "passive"))
      (node (ref "IC13") (pin "6") (pinfunction "V+_6") (pintype "power_in"))
      (node (ref "IC15") (pin "6") (pinfunction "V+_6") (pintype "power_in"))
      (node (ref "IC4") (pin "3") (pinfunction "EN_3") (pintype "bidirectional"))
      (node (ref "IC4") (pin "4") (pinfunction "VIN_4") (pintype "bidirectional"))
      (node (ref "IC5") (pin "7") (pinfunction "VDD_7") (pintype "bidirectional"))
      (node (ref "U7") (pin "1") (pinfunction "VIN_1") (pintype "bidirectional"))
      (node (ref "U7") (pin "2") (pinfunction "EN_2") (pintype "bidirectional"))
      (node (ref "U7") (pin "3") (pinfunction "SS_3") (pintype "bidirectional"))
      (node (ref "U8") (pin "1") (pinfunction "VIN_1") (pintype "bidirectional"))
      (node (ref "U8") (pin "2") (pinfunction "EN_2") (pintype "bidirectional"))
      (node (ref "U8") (pin "3") (pinfunction "SS_3") (pintype "bidirectional"))
    )
    (net (code "4") (name "+5V") (class "Default")
      (node (ref "C13") (pin "1") (pinfunction "1_1") (pintype "passive"))
      (node (ref "C15") (pin "1") (pinfunction "1_1") (pintype "passive"))
      (node (ref "F2") (pin "2") (pinfunction "2_2") (pintype "passive"))
      (node (ref "R36") (pin "2") (pinfunction "2_2") (pintype "passive"))
      (node (ref "U3") (pin "1") (pinfunction "IN_1") (pintype "bidirectional"))
      (node (ref "U4") (pin "1") (pinfunction "IN_1") (pintype "bidirectional"))
      (node (ref "U4") (pin "3") (pinfunction "EN_3") (pintype "bidirectional"))
    )
    (net (code "5") (name "+10V") (class "Default")
      (node (ref "C23") (pin "1") (pinfunction "1_1") (pintype "passive"))
      (node (ref "C24") (pin "1") (pinfunction "1_1") (pintype "passive"))
      (node (ref "C43") (pin "1") (pinfunction "1_1") (pintype "passive"))
      (node (ref "C51") (pin "1") (pinfunction "1_1") (pintype "passive"))
      (node (ref "F4") (pin "1") (pinfunction "1_1") (pintype "passive"))
      (node (ref "IC14") (pin "6") (pinfunction "V+_6") (pintype "power_in"))
      (node (ref "IC6") (pin "6") (pinfunction "V+_6") (pintype "power_in"))
      (node (ref "IC7") (pin "8") (pinfunction "V+_8") (pintype "power_in"))
      (node (ref "IC9") (pin "16") (pinfunction "VDD_16") (pintype "bidirectional"))
    )
    (net (code "6") (name "ADC_CONVST") (class "Default")
      (node (ref "IC10") (pin "8") (pinfunction "PA2_8") (pintype "bidirectional"))
      (node (ref "U5") (pin "6") (pinfunction "CONVST_6") (pintype "bidirectional"))
      (node (ref "U6") (pin "6") (pinfunction "CONVST_6") (pintype "bidirectional"))
    )
    (net (code "7") (name "ADC_CS1") (class "Default")
      (node (ref "IC10") (pin "9") (pinfunction "PA3_9") (pintype "bidirectional"))
      (node (ref "R1") (pin "1") (pinfunction "1_1") (pintype "passive"))
      (node (ref "U5") (pin "9") (pinfunction "DIN_9") (pintype "bidirectional"))
    )
    (net (code "8") (name "ADC_CS2") (class "Default")
      (node (ref "IC10") (pin "10") (pinfunction "PA4_10") (pintype "bidirectional"))
      (node (ref "R44") (pin "1") (pinfunction "1_1") (pintype "passive"))
      (node (ref "U6") (pin "9") (pinfunction "DIN_9") (pintype "bidirectional"))
    )
    (net (code "9") (name "ADC_CURRENT") (class "Default")
      (node (ref "C54") (pin "2") (pinfunction "2_2") (pintype "passive"))
      (node (ref "IC13") (pin "1") (pinfunction "OUT_1") (pintype "output"))
      (node (ref "IC13") (pin "4") (pinfunction "IN-_4") (pintype "input"))
      (node (ref "R20") (pin "1") (pinfunction "1_1") (pintype "passive"))
    )
    (net (code "10") (name "ADC_MISO") (class "Default")
      (node (ref "IC10") (pin "12") (pinfunction "PA6_12") (pintype "bidirectional"))
      (node (ref "U5") (pin "7") (pinfunction "DOUT_7") (pintype "bidirectional"))
      (node (ref "U6") (pin "7") (pinfunction "DOUT_7") (pintype "bidirectional"))
    )
    (net (code "11") (name "ADC_SCK") (class "Default")
      (node (ref "IC10") (pin "11") (pinfunction "PA5_11") (pintype "bidirectional"))
      (node (ref "U5") (pin "8") (pinfunction "SCLK_8") (pintype "bidirectional"))
      (node (ref "U6") (pin "8") (pinfunction "SCLK_8") (pintype "bidirectional"))
    )
    (net (code "12") (name "ADC_VOLTAGE") (class "Default")
      (node (ref "C53") (pin "2") (pinfunction "2_2") (pintype "passive"))
      (node (ref "IC15") (pin "1") (pinfunction "OUT_1") (pintype "output"))
      (node (ref "IC15") (pin "4") (pinfunction "IN-_4") (pintype "input"))
      (node (ref "R18") (pin "1") (pinfunction "1_1") (pintype "passive"))
    )
    (net (code "13") (name "CE") (class "Default")
      (node (ref "R38") (pin "2") (pinfunction "2_2") (pintype "passive"))
      (node (ref "X2") (pin "1") (pinfunction "1_1") (pintype "passive"))
    )
    (net (code "14") (name "CLOCK") (class "Default")
      (node (ref "IC10") (pin "6") (pinfunction "PA0-CK_IN_6") (pintype "bidirectional"))
      (node (ref "Q1") (pin "3") (pinfunction "OUT_3") (pintype "output"))
    )
    (net (code "15") (name "DAC_AUX") (class "Default")
      (node (ref "IC10") (pin "13") (pinfunction "PA7_13") (pintype "bidirectional"))
      (node (ref "IC5") (pin "5") (pinfunction "~{AUX}_5") (pintype "bidirectional"))
    )
    (net (code "16") (name "GND") (class "Default")
      (node (ref "C11") (pin "2") (pinfunction "2_2") (pintype "passive"))
      (node (ref "C12") (pin "2") (pinfunction "2_2") (pintype "passive"))
      (node (ref "C13") (pin "2") (pinfunction "2_2") (pintype "passive"))
      (node (ref "C14") (pin "2") (pinfunction "2_2") (pintype "passive"))
      (node (ref "C15") (pin "2") (pinfunction "2_2") (pintype "passive"))
      (node (ref "C16") (pin "2") (pinfunction "2_2") (pintype "passive"))
      (node (ref "C17") (pin "2") (pinfunction "2_2") (pintype "passive"))
      (node (ref "C18") (pin "2") (pinfunction "2_2") (pintype "passive"))
      (node (ref "C19") (pin "2") (pinfunction "2_2") (pintype "passive"))
      (node (ref "C20") (pin "2") (pinfunction "2_2") (pintype "passive"))
      (node (ref "C21") (pin "2") (pinfunction "2_2") (pintype "passive"))
      (node (ref "C22") (pin "2") (pinfunction "2_2") (pintype "passive"))
      (node (ref "C23") (pin "2") (pinfunction "2_2") (pintype "passive"))
      (node (ref "C24") (pin "2") (pinfunction "2_2") (pintype "passive"))
      (node (ref "C25") (pin "2") (pinfunction "2_2") (pintype "passive"))
      (node (ref "C26") (pin "2") (pinfunction "2_2") (pintype "passive"))
      (node (ref "C27") (pin "2") (pinfunction "2_2") (pintype "passive"))
      (node (ref "C28") (pin "2") (pinfunction "2_2") (pintype "passive"))
      (node (ref "C29") (pin "2") (pinfunction "2_2") (pintype "passive"))
      (node (ref "C30") (pin "2") (pinfunction "2_2") (pintype "passive"))
      (node (ref "C31") (pin "2") (pinfunction "2_2") (pintype "passive"))
      (node (ref "C32") (pin "2") (pinfunction "2_2") (pintype "passive"))
      (node (ref "C34") (pin "2") (pinfunction "2_2") (pintype "passive"))
      (node (ref "C35") (pin "2") (pinfunction "2_2") (pintype "passive"))
      (node (ref "C36") (pin "2") (pinfunction "2_2") (pintype "passive"))
      (node (ref "C38") (pin "2") (pinfunction "2_2") (pintype "passive"))
      (node (ref "C39") (pin "2") (pinfunction "2_2") (pintype "passive"))
      (node (ref "C40") (pin "2") (pinfunction "2_2") (pintype "passive"))
      (node (ref "C41") (pin "2") (pinfunction "2_2") (pintype "passive"))
      (node (ref "C42") (pin "2") (pinfunction "2_2") (pintype "passive"))
      (node (ref "C43") (pin "2") (pinfunction "2_2") (pintype "passive"))
      (node (ref "C44") (pin "2") (pinfunction "2_2") (pintype "passive"))
      (node (ref "C45") (pin "2") (pinfunction "2_2") (pintype "passive"))
      (node (ref "C46") (pin "2") (pinfunction "2_2") (pintype "passive"))
      (node (ref "C49") (pin "2") (pinfunction "2_2") (pintype "passive"))
      (node (ref "C51") (pin "2") (pinfunction "2_2") (pintype "passive"))
      (node (ref "C52") (pin "2") (pinfunction "2_2") (pintype "passive"))
      (node (ref "C7") (pin "2") (pinfunction "2_2") (pintype "passive"))
      (node (ref "C8") (pin "2") (pinfunction "2_2") (pintype "passive"))
      (node (ref "IC1") (pin "15") (pinfunction "GND2_15") (pintype "bidirectional"))
      (node (ref "IC1") (pin "9") (pinfunction "GND2_9") (pintype "bidirectional"))
      (node (ref "IC10") (pin "16") (pinfunction "VSS_16") (pintype "bidirectional"))
      (node (ref "IC10") (pin "32") (pinfunction "VSS_32") (pintype "bidirectional"))
      (node (ref "IC11") (pin "4") (pinfunction "GND1_4") (pintype "bidirectional"))
      (node (ref "IC13") (pin "2") (pinfunction "V-_2") (pintype "power_in"))
      (node (ref "IC14") (pin "2") (pinfunction "V-_2") (pintype "power_in"))
      (node (ref "IC15") (pin "2") (pinfunction "V-_2") (pintype "power_in"))
      (node (ref "IC2") (pin "4") (pinfunction "0V_4") (pintype "power_in"))
      (node (ref "IC3") (pin "4") (pinfunction "0V_4") (pintype "power_in"))
      (node (ref "IC4") (pin "2") (pinfunction "GND_2") (pintype "bidirectional"))
      (node (ref "IC5") (pin "2") (pinfunction "ADDR_2") (pintype "bidirectional"))
      (node (ref "IC5") (pin "8") (pinfunction "GND_8") (pintype "bidirectional"))
      (node (ref "IC6") (pin "2") (pinfunction "V-_2") (pintype "power_in"))
      (node (ref "IC7") (pin "4") (pinfunction "V-_4") (pintype "power_in"))
      (node (ref "IC9") (pin "7") (pinfunction "VSS_7") (pintype "bidirectional"))
      (node (ref "IC9") (pin "8") (pinfunction "GND_8") (pintype "bidirectional"))
      (node (ref "J2") (pin "3") (pinfunction "3_3") (pintype "passive"))
      (node (ref "J2") (pin "5") (pinfunction "5_5") (pintype "passive"))
      (node (ref "Q1") (pin "2") (pinfunction "GND_2") (pintype "power_in"))
      (node (ref "R15") (pin "1") (pinfunction "1_1") (pintype "passive"))
      (node (ref "R17") (pin "1") (pinfunction "1_1") (pintype "passive"))
      (node (ref "R19") (pin "1") (pinfunction "1_1") (pintype "passive"))
      (node (ref "R21") (pin "1") (pinfunction "1_1") (pintype "passive"))
      (node (ref "R22") (pin "1") (pinfunction "1_1") (pintype "passive"))
      (node (ref "R25") (pin "1") (pinfunction "1_1") (pintype "passive"))
      (node (ref "R36") (pin "1") (pinfunction "1_1") (pintype "passive"))
      (node (ref "R37") (pin "1") (pinfunction "1_1") (pintype "passive"))
      (node (ref "R4") (pin "1") (pinfunction "1_1") (pintype "passive"))
      (node (ref "R42") (pin "1") (pinfunction "1_1") (pintype "passive"))
      (node (ref "R43") (pin "1") (pinfunction "1_1") (pintype "passive"))
      (node (ref "TP2") (pin "TP") (pinfunction "TP_TP") (pintype "input"))
      (node (ref "U2") (pin "2") (pinfunction "GND_2") (pintype "bidirectional"))
      (node (ref "U3") (pin "2") (pinfunction "GND_2") (pintype "bidirectional"))
      (node (ref "U4") (pin "2") (pinfunction "GND_2") (pintype "bidirectional"))
      (node (ref "U5") (pin "5") (pinfunction "GND_5") (pintype "bidirectional"))
      (node (ref "U6") (pin "5") (pinfunction "GND_5") (pintype "bidirectional"))
      (node (ref "U7") (pin "7") (pinfunction "GND_F_7") (pintype "bidirectional"))
      (node (ref "U7") (pin "8") (pinfunction "GND_S_8") (pintype "bidirectional"))
      (node (ref "U8") (pin "7") (pinfunction "GND_F_7") (pintype "bidirectional"))
      (node (ref "U8") (pin "8") (pinfunction "GND_S_8") (pintype "bidirectional"))
    )
    (net (code "17") (name "GNDIO") (class "Default")
      (node (ref "C10") (pin "2") (pinfunction "2_2") (pintype "passive"))
      (node (ref "C47") (pin "2") (pinfunction "2_2") (pintype "passive"))
      (node (ref "C48") (pin "2") (pinfunction "2_2") (pintype "passive"))
      (node (ref "C5") (pin "2") (pinfunction "2_2") (pintype "passive"))
      (node (ref "C50") (pin "2") (pinfunction "2_2") (pintype "passive"))
      (node (ref "C6") (pin "2") (pinfunction "2_2") (pintype "passive"))
      (node (ref "C9") (pin "2") (pinfunction "2_2") (pintype "passive"))
      (node (ref "IC1") (pin "2") (pinfunction "GND1_2") (pintype "bidirectional"))
      (node (ref "IC1") (pin "8") (pinfunction "GND1_8") (pintype "bidirectional"))
      (node (ref "IC11") (pin "5") (pinfunction "GND2_5") (pintype "bidirectional"))
      (node (ref "IC12") (pin "3") (pinfunction "ADR1_3") (pintype "passive"))
      (node (ref "IC12") (pin "4") (pinfunction "ADR0_4") (pintype "passive"))
      (node (ref "IC12") (pin "5") (pinfunction "ADIN_5") (pintype "input"))
      (node (ref "IC12") (pin "6") (pinfunction "GND_6") (pintype "power_in"))
      (node (ref "IC2") (pin "1") (pinfunction "GND_1") (pintype "power_in"))
      (node (ref "IC3") (pin "1") (pinfunction "GND_1") (pintype "power_in"))
      (node (ref "J1") (pin "A1/B12") (pinfunction "GND_A1/B12") (pintype "passive"))
      (node (ref "J1") (pin "B1/A12") (pinfunction "GND_B1/A12") (pintype "passive"))
      (node (ref "R11") (pin "1") (pinfunction "1_1") (pintype "passive"))
      (node (ref "R12") (pin "1") (pinfunction "1_1") (pintype "passive"))
      (node (ref "R13") (pin "1") (pinfunction "1_1") (pintype "passive"))
      (node (ref "TP1") (pin "TP") (pinfunction "TP_TP") (pintype "input"))
      (node (ref "U1") (pin "2") (pinfunction "2_2") (pintype "passive"))
    )
    (net (code "18") (name "MUX_A0") (class "Default")
      (node (ref "IC10") (pin "26") (pinfunction "PB3_26") (pintype "bidirectional"))
      (node (ref "IC9") (pin "10") (pinfunction "A0_10") (pintype "bidirectional"))
    )
    (net (code "19") (name "MUX_A1") (class "Default")
      (node (ref "IC10") (pin "27") (pinfunction "PB4_27") (pintype "bidirectional"))
      (node (ref "IC9") (pin "9") (pinfunction "A1_9") (pintype "bidirectional"))
    )
    (net (code "20") (name "MUX_GAIN1") (class "Default")
      (node (ref "C4") (pin "2") (pinfunction "2_2") (pintype "passive"))
      (node (ref "IC9") (pin "1") (pinfunction "S1B_1") (pintype "bidirectional"))
      (node (ref "IC9") (pin "12") (pinfunction "S1A_12") (pintype "bidirectional"))
      (node (ref "R5") (pin "2") (pinfunction "2_2") (pintype "passive"))
    )
    (net (code "21") (name "MUX_GAIN2") (class "Default")
      (node (ref "C3") (pin "2") (pinfunction "2_2") (pintype "passive"))
      (node (ref "IC9") (pin "14") (pinfunction "S2A_14") (pintype "bidirectional"))
      (node (ref "IC9") (pin "5") (pinfunction "S2B_5") (pintype "bidirectional"))
      (node (ref "R7") (pin "2") (pinfunction "2_2") (pintype "passive"))
    )
    (net (code "22") (name "MUX_GAIN3") (class "Default")
      (node (ref "C2") (pin "2") (pinfunction "2_2") (pintype "passive"))
      (node (ref "IC9") (pin "15") (pinfunction "S3A_15") (pintype "bidirectional"))
      (node (ref "IC9") (pin "2") (pinfunction "S3B_2") (pintype "bidirectional"))
      (node (ref "R27") (pin "2") (pinfunction "2_2") (pintype "passive"))
    )
    (net (code "23") (name "MUX_GAIN4") (class "Default")
      (node (ref "C1") (pin "2") (pinfunction "2_2") (pintype "passive"))
      (node (ref "IC9") (pin "11") (pinfunction "S4A_11") (pintype "bidirectional"))
      (node (ref "IC9") (pin "4") (pinfunction "S4B_4") (pintype "bidirectional"))
      (node (ref "R29") (pin "2") (pinfunction "2_2") (pintype "passive"))
    )
    (net (code "24") (name "MUX_IN") (class "Default")
      (node (ref "IC7") (pin "1") (pinfunction "OUT_1") (pintype "output"))
      (node (ref "IC9") (pin "13") (pinfunction "DA_13") (pintype "bidirectional"))
    )
    (net (code "25") (name "Net-(C54-Pad1)") (class "Default")
      (node (ref "C54") (pin "1") (pinfunction "1_1") (pintype "passive"))
      (node (ref "R3") (pin "2") (pinfunction "2_2") (pintype "passive"))
      (node (ref "R4") (pin "2") (pinfunction "2_2") (pintype "passive"))
      (node (ref "R47") (pin "2") (pinfunction "2_2") (pintype "passive"))
    )
    (net (code "26") (name "Net-(IC1-PDEN)") (class "Default")
      (node (ref "C5") (pin "1") (pinfunction "1_1") (pintype "passive"))
      (node (ref "IC1") (pin "3") (pinfunction "VDD1_3") (pintype "bidirectional"))
      (node (ref "IC1") (pin "4") (pinfunction "PDEN_4") (pintype "bidirectional"))
      (node (ref "IC1") (pin "5") (pinfunction "SPU_5") (pintype "bidirectional"))
    )
    (net (code "27") (name "Net-(IC1-UD+)") (class "Default")
      (node (ref "IC1") (pin "7") (pinfunction "UD+_7") (pintype "bidirectional"))
      (node (ref "R9") (pin "2") (pinfunction "2_2") (pintype "passive"))
    )
    (net (code "28") (name "Net-(IC1-UD-)") (class "Default")
      (node (ref "IC1") (pin "6") (pinfunction "UD-_6") (pintype "bidirectional"))
      (node (ref "R10") (pin "2") (pinfunction "2_2") (pintype "passive"))
    )
    (net (code "29") (name "Net-(IC2-+VO)") (class "Default")
      (node (ref "C11") (pin "1") (pinfunction "1_1") (pintype "passive"))
      (node (ref "F2") (pin "1") (pinfunction "1_1") (pintype "passive"))
      (node (ref "IC2") (pin "5") (pinfunction "+VO_5") (pintype "power_in"))
    )
    (net (code "30") (name "Net-(IC2-VIN)") (class "Default")
      (node (ref "IC2") (pin "2") (pinfunction "VIN_2") (pintype "power_in"))
      (node (ref "L1") (pin "1") (pinfunction "1_1") (pintype "passive"))
    )
    (net (code "31") (name "Net-(IC3-+VO)") (class "Default")
      (node (ref "C12") (pin "1") (pinfunction "1_1") (pintype "passive"))
      (node (ref "F6") (pin "1") (pinfunction "1_1") (pintype "passive"))
      (node (ref "IC3") (pin "5") (pinfunction "+VO_5") (pintype "power_in"))
    )
    (net (code "32") (name "Net-(IC3-VIN)") (class "Default")
      (node (ref "IC3") (pin "2") (pinfunction "VIN_2") (pintype "power_in"))
      (node (ref "L2") (pin "1") (pinfunction "1_1") (pintype "passive"))
    )
    (net (code "33") (name "Net-(IC5-OUT)") (class "Default")
      (node (ref "IC5") (pin "6") (pinfunction "OUT_6") (pintype "bidirectional"))
      (node (ref "R23") (pin "2") (pinfunction "2_2") (pintype "passive"))
    )
    (net (code "34") (name "Net-(IC5-SCL)") (class "Default")
      (node (ref "IC5") (pin "3") (pinfunction "SCL_3") (pintype "bidirectional"))
      (node (ref "R39") (pin "2") (pinfunction "2_2") (pintype "passive"))
    )
    (net (code "35") (name "Net-(IC5-SDA)") (class "Default")
      (node (ref "IC5") (pin "4") (pinfunction "SDA_4") (pintype "bidirectional"))
      (node (ref "R40") (pin "2") (pinfunction "2_2") (pintype "passive"))
    )
    (net (code "36") (name "Net-(IC6A-IN+)") (class "Default")
      (node (ref "C42") (pin "1") (pinfunction "1_1") (pintype "passive"))
      (node (ref "IC6") (pin "3") (pinfunction "IN+_3") (pintype "input"))
      (node (ref "R23") (pin "1") (pinfunction "1_1") (pintype "passive"))
    )
    (net (code "37") (name "Net-(IC6A-IN-)") (class "Default")
      (node (ref "C53") (pin "1") (pinfunction "1_1") (pintype "passive"))
      (node (ref "C55") (pin "2") (pinfunction "2_2") (pintype "passive"))
      (node (ref "IC6") (pin "4") (pinfunction "IN-_4") (pintype "input"))
      (node (ref "R24") (pin "1") (pinfunction "1_1") (pintype "passive"))
      (node (ref "R25") (pin "2") (pinfunction "2_2") (pintype "passive"))
      (node (ref "R46") (pin "2") (pinfunction "2_2") (pintype "passive"))
    )
    (net (code "38") (name "Net-(IC6A-OUT)") (class "Default")
      (node (ref "C55") (pin "1") (pinfunction "1_1") (pintype "passive"))
      (node (ref "IC6") (pin "1") (pinfunction "OUT_1") (pintype "output"))
      (node (ref "R38") (pin "1") (pinfunction "1_1") (pintype "passive"))
    )
    (net (code "39") (name "Net-(IC7B-IN-)") (class "Default")
      (node (ref "IC7") (pin "6") (pinfunction "IN-_6") (pintype "input"))
      (node (ref "IC7") (pin "7") (pinfunction "OUT_7") (pintype "output"))
      (node (ref "R24") (pin "2") (pinfunction "2_2") (pintype "passive"))
    )
    (net (code "40") (name "Net-(IC10-BOOT0-PH3)") (class "Default")
      (node (ref "IC10") (pin "31") (pinfunction "BOOT0-PH3_31") (pintype "bidirectional"))
      (node (ref "R22") (pin "2") (pinfunction "2_2") (pintype "passive"))
    )
    (net (code "41") (name "Net-(IC12-INTVCC)") (class "Default")
      (node (ref "C47") (pin "1") (pinfunction "1_1") (pintype "passive"))
      (node (ref "F1") (pin "1") (pinfunction "1_1") (pintype "passive"))
      (node (ref "IC12") (pin "1") (pinfunction "VDD_1") (pintype "passive"))
      (node (ref "IC12") (pin "12") (pinfunction "SENSE+_12") (pintype "input"))
      (node (ref "IC12") (pin "2") (pinfunction "INTVCC_2") (pintype "passive"))
      (node (ref "R32") (pin "1") (pinfunction "1_1") (pintype "passive"))
    )
    (net (code "42") (name "Net-(IC13A-IN+)") (class "Default")
      (node (ref "C45") (pin "1") (pinfunction "1_1") (pintype "passive"))
      (node (ref "IC13") (pin "3") (pinfunction "IN+_3") (pintype "input"))
      (node (ref "R47") (pin "1") (pinfunction "1_1") (pintype "passive"))
    )
    (net (code "43") (name "Net-(IC14A-IN+)") (class "Default")
      (node (ref "IC14") (pin "3") (pinfunction "IN+_3") (pintype "input"))
      (node (ref "IC9") (pin "3") (pinfunction "DB_3") (pintype "bidirectional"))
    )
    (net (code "44") (name "Net-(IC14A-IN-)") (class "Default")
      (node (ref "IC14") (pin "1") (pinfunction "OUT_1") (pintype "output"))
      (node (ref "IC14") (pin "4") (pinfunction "IN-_4") (pintype "input"))
      (node (ref "R3") (pin "1") (pinfunction "1_1") (pintype "passive"))
    )
    (net (code "45") (name "Net-(IC15A-IN+)") (class "Default")
      (node (ref "C46") (pin "1") (pinfunction "1_1") (pintype "passive"))
      (node (ref "IC15") (pin "3") (pinfunction "IN+_3") (pintype "input"))
      (node (ref "R46") (pin "1") (pinfunction "1_1") (pintype "passive"))
    )
    (net (code "46") (name "Net-(J1-CC1)") (class "Default")
      (node (ref "J1") (pin "A5") (pinfunction "CC1_A5") (pintype "bidirectional"))
      (node (ref "R12") (pin "2") (pinfunction "2_2") (pintype "passive"))
    )
    (net (code "47") (name "Net-(J1-CC2)") (class "Default")
      (node (ref "J1") (pin "B5") (pinfunction "CC2_B5") (pintype "bidirectional"))
      (node (ref "R11") (pin "2") (pinfunction "2_2") (pintype "passive"))
    )
    (net (code "48") (name "Net-(J1-DN-PadA7)") (class "Default")
      (node (ref "J1") (pin "A7") (pinfunction "DN_A7") (pintype "bidirectional"))
      (node (ref "J1") (pin "B7") (pinfunction "DN_B7") (pintype "bidirectional"))
      (node (ref "U1") (pin "1") (pinfunction "1_1") (pintype "bidirectional"))
    )
    (net (code "49") (name "Net-(J1-DP-PadA6)") (class "Default")
      (node (ref "J1") (pin "A6") (pinfunction "DP_A6") (pintype "bidirectional"))
      (node (ref "J1") (pin "B6") (pinfunction "DP_B6") (pintype "bidirectional"))
      (node (ref "U1") (pin "3") (pinfunction "3_3") (pintype "bidirectional"))
    )
    (net (code "50") (name "Net-(J1-SHLD-PadP1)") (class "Default")
      (node (ref "J1") (pin "P1") (pinfunction "SHLD_P1") (pintype "bidirectional"))
      (node (ref "J1") (pin "P2") (pinfunction "SHLD_P2") (pintype "bidirectional"))
      (node (ref "J1") (pin "P3") (pinfunction "SHLD_P3") (pintype "bidirectional"))
      (node (ref "J1") (pin "P4") (pinfunction "SHLD_P4") (pintype "bidirectional"))
      (node (ref "J1") (pin "S1") (pinfunction "SHLD_S1") (pintype "bidirectional"))
      (node (ref "J1") (pin "S2") (pinfunction "SHLD_S2") (pintype "bidirectional"))
      (node (ref "J1") (pin "S3") (pinfunction "SHLD_S3") (pintype "bidirectional"))
      (node (ref "J1") (pin "S4") (pinfunction "SHLD_S4") (pintype "bidirectional"))
      (node (ref "J1") (pin "S5") (pinfunction "SHLD_S5") (pintype "bidirectional"))
      (node (ref "J1") (pin "S6") (pinfunction "SHLD_S6") (pintype "bidirectional"))
      (node (ref "J1") (pin "S7") (pinfunction "SHLD_S7") (pintype "bidirectional"))
      (node (ref "J1") (pin "S8") (pinfunction "SHLD_S8") (pintype "bidirectional"))
      (node (ref "R13") (pin "2") (pinfunction "2_2") (pintype "passive"))
    )
    (net (code "51") (name "Net-(LED3A-A)") (class "Default")
      (node (ref "LED3") (pin "A1") (pinfunction "A_A1") (pintype "passive"))
      (node (ref "LED3") (pin "A2") (pinfunction "A_A2") (pintype "passive"))
      (node (ref "R41") (pin "2") (pinfunction "2_2") (pintype "passive"))
    )
    (net (code "52") (name "Net-(R5-Pad1)") (class "Default")
      (node (ref "R5") (pin "1") (pinfunction "1_1") (pintype "passive"))
      (node (ref "R8") (pin "2") (pinfunction "2_2") (pintype "passive"))
    )
    (net (code "53") (name "Net-(R6-Pad2)") (class "Default")
      (node (ref "R6") (pin "2") (pinfunction "2_2") (pintype "passive"))
      (node (ref "R7") (pin "1") (pinfunction "1_1") (pintype "passive"))
    )
    (net (code "54") (name "Net-(R9-Pad1)") (class "Default")
      (node (ref "R9") (pin "1") (pinfunction "1_1") (pintype "passive"))
      (node (ref "U1") (pin "4") (pinfunction "4_4") (pintype "bidirectional"))
    )
    (net (code "55") (name "Net-(R10-Pad1)") (class "Default")
      (node (ref "R10") (pin "1") (pinfunction "1_1") (pintype "passive"))
      (node (ref "U1") (pin "6") (pinfunction "6_6") (pintype "bidirectional"))
    )
    (net (code "56") (name "Net-(R26-Pad2)") (class "Default")
      (node (ref "R26") (pin "2") (pinfunction "2_2") (pintype "passive"))
      (node (ref "R27") (pin "1") (pinfunction "1_1") (pintype "passive"))
    )
    (net (code "57") (name "Net-(R28-Pad2)") (class "Default")
      (node (ref "R28") (pin "2") (pinfunction "2_2") (pintype "passive"))
      (node (ref "R29") (pin "1") (pinfunction "1_1") (pintype "passive"))
    )
    (net (code "58") (name "Net-(R35-Pad2)") (class "Default")
      (node (ref "R35") (pin "2") (pinfunction "2_2") (pintype "passive"))
      (node (ref "X2") (pin "G1") (pinfunction "G1_G1") (pintype "passive"))
    )
    (net (code "59") (name "Net-(R42-Pad2)") (class "Default")
      (node (ref "R42") (pin "2") (pinfunction "2_2") (pintype "passive"))
      (node (ref "X2") (pin "2") (pinfunction "2_2") (pintype "passive"))
      (node (ref "X2") (pin "4") (pinfunction "4_4") (pintype "passive"))
      (node (ref "X2") (pin "6") (pinfunction "6_6") (pintype "passive"))
      (node (ref "X2") (pin "7") (pinfunction "7_7") (pintype "passive"))
      (node (ref "X2") (pin "8") (pinfunction "8_8") (pintype "passive"))
      (node (ref "X2") (pin "9") (pinfunction "9_9") (pintype "passive"))
      (node (ref "X2") (pin "G2") (pinfunction "G2_G2") (pintype "passive"))
    )
    (net (code "60") (name "Net-(U2-IN)") (class "Default")
      (node (ref "C20") (pin "1") (pinfunction "1_1") (pintype "passive"))
      (node (ref "F6") (pin "2") (pinfunction "2_2") (pintype "passive"))
      (node (ref "R37") (pin "2") (pinfunction "2_2") (pintype "passive"))
      (node (ref "U2") (pin "1") (pinfunction "IN_1") (pintype "bidirectional"))
    )
    (net (code "61") (name "Net-(U2-NC{slash}ADJ)") (class "Default")
      (node (ref "R16") (pin "1") (pinfunction "1_1") (pintype "passive"))
      (node (ref "R17") (pin "2") (pinfunction "2_2") (pintype "passive"))
      (node (ref "U2") (pin "4") (pinfunction "NC/ADJ_4") (pintype "bidirectional"))
    )
    (net (code "62") (name "Net-(U2-OUT)") (class "Default")
      (node (ref "C19") (pin "1") (pinfunction "1_1") (pintype "passive"))
      (node (ref "F4") (pin "2") (pinfunction "2_2") (pintype "passive"))
      (node (ref "R16") (pin "2") (pinfunction "2_2") (pintype "passive"))
      (node (ref "U2") (pin "5") (pinfunction "OUT_5") (pintype "bidirectional"))
    )
    (net (code "63") (name "Net-(U3-NC{slash}ADJ)") (class "Default")
      (node (ref "R14") (pin "1") (pinfunction "1_1") (pintype "passive"))
      (node (ref "R15") (pin "2") (pinfunction "2_2") (pintype "passive"))
      (node (ref "U3") (pin "4") (pinfunction "NC/ADJ_4") (pintype "bidirectional"))
    )
    (net (code "64") (name "Net-(U3-OUT)") (class "Default")
      (node (ref "C14") (pin "1") (pinfunction "1_1") (pintype "passive"))
      (node (ref "F3") (pin "2") (pinfunction "2_2") (pintype "passive"))
      (node (ref "R14") (pin "2") (pinfunction "2_2") (pintype "passive"))
      (node (ref "U3") (pin "5") (pinfunction "OUT_5") (pintype "bidirectional"))
    )
    (net (code "65") (name "Net-(U4-OUT)") (class "Default")
      (node (ref "C16") (pin "1") (pinfunction "1_1") (pintype "passive"))
      (node (ref "F5") (pin "2") (pinfunction "2_2") (pintype "passive"))
      (node (ref "U4") (pin "5") (pinfunction "OUT_5") (pintype "bidirectional"))
    )
    (net (code "66") (name "Net-(U5-AINN)") (class "Default")
      (node (ref "C33") (pin "2") (pinfunction "2_2") (pintype "passive"))
      (node (ref "R19") (pin "2") (pinfunction "2_2") (pintype "passive"))
      (node (ref "U5") (pin "4") (pinfunction "AINN_4") (pintype "bidirectional"))
    )
    (net (code "67") (name "Net-(U5-AINP)") (class "Default")
      (node (ref "C33") (pin "1") (pinfunction "1_1") (pintype "passive"))
      (node (ref "R18") (pin "2") (pinfunction "2_2") (pintype "passive"))
      (node (ref "U5") (pin "3") (pinfunction "AINP_3") (pintype "bidirectional"))
    )
    (net (code "68") (name "Net-(U5-REF)") (class "Default")
      (node (ref "C30") (pin "1") (pinfunction "1_1") (pintype "passive"))
      (node (ref "U5") (pin "1") (pinfunction "REF_1") (pintype "bidirectional"))
      (node (ref "U7") (pin "5") (pinfunction "OUT_S_5") (pintype "bidirectional"))
      (node (ref "U7") (pin "6") (pinfunction "OUT_F_6") (pintype "bidirectional"))
    )
    (net (code "69") (name "Net-(U6-AINN)") (class "Default")
      (node (ref "C37") (pin "2") (pinfunction "2_2") (pintype "passive"))
      (node (ref "R21") (pin "2") (pinfunction "2_2") (pintype "passive"))
      (node (ref "U6") (pin "4") (pinfunction "AINN_4") (pintype "bidirectional"))
    )
    (net (code "70") (name "Net-(U6-AINP)") (class "Default")
      (node (ref "C37") (pin "1") (pinfunction "1_1") (pintype "passive"))
      (node (ref "R20") (pin "2") (pinfunction "2_2") (pintype "passive"))
      (node (ref "U6") (pin "3") (pinfunction "AINP_3") (pintype "bidirectional"))
    )
    (net (code "71") (name "Net-(U6-REF)") (class "Default")
      (node (ref "C34") (pin "1") (pinfunction "1_1") (pintype "passive"))
      (node (ref "U6") (pin "1") (pinfunction "REF_1") (pintype "bidirectional"))
      (node (ref "U8") (pin "5") (pinfunction "OUT_S_5") (pintype "bidirectional"))
      (node (ref "U8") (pin "6") (pinfunction "OUT_F_6") (pintype "bidirectional"))
    )
    (net (code "72") (name "Net-(U7-FILT)") (class "Default")
      (node (ref "C28") (pin "1") (pinfunction "1_1") (pintype "passive"))
      (node (ref "U7") (pin "4") (pinfunction "FILT_4") (pintype "bidirectional"))
    )
    (net (code "73") (name "Net-(U8-FILT)") (class "Default")
      (node (ref "C29") (pin "1") (pinfunction "1_1") (pintype "passive"))
      (node (ref "U8") (pin "4") (pinfunction "FILT_4") (pintype "bidirectional"))
    )
    (net (code "74") (name "PWR_ENABLE") (class "Default")
      (node (ref "IC10") (pin "2") (pinfunction "PC14-OSC32_IN_2") (pintype "bidirectional"))
      (node (ref "R43") (pin "2") (pinfunction "2_2") (pintype "passive"))
      (node (ref "U2") (pin "3") (pinfunction "EN_3") (pintype "bidirectional"))
      (node (ref "U3") (pin "3") (pinfunction "EN_3") (pintype "bidirectional"))
    )
    (net (code "75") (name "RE") (class "Default")
      (node (ref "IC7") (pin "5") (pinfunction "IN+_5") (pintype "input"))
      (node (ref "X2") (pin "3") (pinfunction "3_3") (pintype "passive"))
    )
    (net (code "76") (name "SCL") (class "Default")
      (node (ref "IC10") (pin "29") (pinfunction "PB6_29") (pintype "bidirectional"))
      (node (ref "IC11") (pin "3") (pinfunction "SCL1_3") (pintype "bidirectional"))
      (node (ref "R34") (pin "1") (pinfunction "1_1") (pintype "passive"))
      (node (ref "R39") (pin "1") (pinfunction "1_1") (pintype "passive"))
    )
    (net (code "77") (name "SCL_ISO") (class "Default")
      (node (ref "IC11") (pin "6") (pinfunction "SCL2_6") (pintype "bidirectional"))
      (node (ref "IC12") (pin "7") (pinfunction "SCL_7") (pintype "input"))
      (node (ref "R31") (pin "1") (pinfunction "1_1") (pintype "passive"))
    )
    (net (code "78") (name "SDA") (class "Default")
      (node (ref "IC10") (pin "30") (pinfunction "PB7_30") (pintype "bidirectional"))
      (node (ref "IC11") (pin "2") (pinfunction "SDA1_2") (pintype "bidirectional"))
      (node (ref "R33") (pin "1") (pinfunction "1_1") (pintype "passive"))
      (node (ref "R40") (pin "1") (pinfunction "1_1") (pintype "passive"))
    )
    (net (code "79") (name "SDA_ISO") (class "Default")
      (node (ref "IC11") (pin "7") (pinfunction "SDA2_7") (pintype "bidirectional"))
      (node (ref "IC12") (pin "8") (pinfunction "SDAI_8") (pintype "input"))
      (node (ref "IC12") (pin "9") (pinfunction "SDAO_9") (pintype "open_collector"))
      (node (ref "R30") (pin "1") (pinfunction "1_1") (pintype "passive"))
    )
    (net (code "80") (name "STATUS_BAD") (class "Default")
      (node (ref "IC10") (pin "15") (pinfunction "PB1_15") (pintype "bidirectional"))
      (node (ref "LED3") (pin "C1") (pinfunction "C_C1") (pintype "passive"))
    )
    (net (code "81") (name "STATUS_GOOD") (class "Default")
      (node (ref "IC10") (pin "14") (pinfunction "PB0_14") (pintype "bidirectional"))
      (node (ref "LED3") (pin "C2") (pinfunction "C_C2") (pintype "passive"))
    )
    (net (code "82") (name "SWCLK") (class "Default")
      (node (ref "IC10") (pin "24") (pinfunction "PA14_24") (pintype "bidirectional"))
      (node (ref "J2") (pin "4") (pinfunction "4_4") (pintype "passive"))
    )
    (net (code "83") (name "SWDIO") (class "Default")
      (node (ref "IC10") (pin "23") (pinfunction "PA13_23") (pintype "bidirectional"))
      (node (ref "J2") (pin "2") (pinfunction "2_2") (pintype "passive"))
    )
    (net (code "84") (name "USB_DM") (class "Default")
      (node (ref "IC1") (pin "11") (pinfunction "DD-_11") (pintype "bidirectional"))
      (node (ref "IC10") (pin "21") (pinfunction "PA11_21") (pintype "bidirectional"))
    )
    (net (code "85") (name "USB_DP") (class "Default")
      (node (ref "IC1") (pin "10") (pinfunction "DD+_10") (pintype "bidirectional"))
      (node (ref "IC10") (pin "22") (pinfunction "PA12_22") (pintype "bidirectional"))
    )
    (net (code "86") (name "VBUS") (class "Default")
      (node (ref "C10") (pin "1") (pinfunction "1_1") (pintype "passive"))
      (node (ref "C50") (pin "1") (pinfunction "1_1") (pintype "passive"))
      (node (ref "C6") (pin "1") (pinfunction "1_1") (pintype "passive"))
      (node (ref "C9") (pin "1") (pinfunction "1_1") (pintype "passive"))
      (node (ref "IC1") (pin "1") (pinfunction "VBUS1_1") (pintype "bidirectional"))
      (node (ref "IC11") (pin "8") (pinfunction "VCC2_8") (pintype "bidirectional"))
      (node (ref "IC12") (pin "11") (pinfunction "SENSE-_11") (pintype "input"))
      (node (ref "L1") (pin "2") (pinfunction "2_2") (pintype "passive"))
      (node (ref "L2") (pin "2") (pinfunction "2_2") (pintype "passive"))
      (node (ref "R30") (pin "2") (pinfunction "2_2") (pintype "passive"))
      (node (ref "R31") (pin "2") (pinfunction "2_2") (pintype "passive"))
      (node (ref "R32") (pin "2") (pinfunction "2_2") (pintype "passive"))
    )
    (net (code "87") (name "VBUS_IN") (class "Default")
      (node (ref "C48") (pin "1") (pinfunction "1_1") (pintype "passive"))
      (node (ref "F1") (pin "2") (pinfunction "2_2") (pintype "passive"))
      (node (ref "J1") (pin "A4/B9") (pinfunction "VBUS_A4/B9") (pintype "power_in"))
      (node (ref "J1") (pin "B4/A9") (pinfunction "VBUS_B4/A9") (pintype "power_in"))
      (node (ref "U1") (pin "5") (pinfunction "5_5") (pintype "passive"))
    )
    (net (code "88") (name "VREF") (class "Default")
      (node (ref "C18") (pin "1") (pinfunction "1_1") (pintype "passive"))
      (node (ref "C21") (pin "1") (pinfunction "1_1") (pintype "passive"))
      (node (ref "C44") (pin "1") (pinfunction "1_1") (pintype "passive"))
      (node (ref "IC4") (pin "5") (pinfunction "VREF_5") (pintype "bidirectional"))
      (node (ref "IC5") (pin "1") (pinfunction "REF_1") (pintype "bidirectional"))
      (node (ref "IC7") (pin "3") (pinfunction "IN+_3") (pintype "input"))
      (node (ref "R35") (pin "1") (pinfunction "1_1") (pintype "passive"))
    )
    (net (code "89") (name "WE") (class "Default")
      (node (ref "C1") (pin "1") (pinfunction "1_1") (pintype "passive"))
      (node (ref "C2") (pin "1") (pinfunction "1_1") (pintype "passive"))
      (node (ref "C3") (pin "1") (pinfunction "1_1") (pintype "passive"))
      (node (ref "C4") (pin "1") (pinfunction "1_1") (pintype "passive"))
      (node (ref "IC7") (pin "2") (pinfunction "IN-_2") (pintype "input"))
      (node (ref "R26") (pin "1") (pinfunction "1_1") (pintype "passive"))
      (node (ref "R28") (pin "1") (pinfunction "1_1") (pintype "passive"))
      (node (ref "R6") (pin "1") (pinfunction "1_1") (pintype "passive"))
      (node (ref "R8") (pin "1") (pinfunction "1_1") (pintype "passive"))
      (node (ref "X2") (pin "5") (pinfunction "5_5") (pintype "passive"))
    )
    (net (code "90") (name "unconnected-(IC10-PA1-Pad7)") (class "Default")
      (node (ref "IC10") (pin "7") (pinfunction "PA1_7") (pintype "bidirectional"))
    )
    (net (code "91") (name "unconnected-(IC10-PA9-Pad19)") (class "Default")
      (node (ref "IC10") (pin "19") (pinfunction "PA9_19") (pintype "bidirectional"))
    )
    (net (code "92") (name "unconnected-(IC10-PA10-Pad20)") (class "Default")
      (node (ref "IC10") (pin "20") (pinfunction "PA10_20") (pintype "bidirectional"))
    )
    (net (code "93") (name "unconnected-(IC10-PA15-Pad25)") (class "Default")
      (node (ref "IC10") (pin "25") (pinfunction "PA15_25") (pintype "bidirectional"))
    )
    (net (code "94") (name "unconnected-(IC10-PC15-OSC32_OUT-Pad3)") (class "Default")
      (node (ref "IC10") (pin "3") (pinfunction "PC15-OSC32_OUT_3") (pintype "bidirectional"))
    )
    (net (code "95") (name "unconnected-(IC12-~{ALERT}-Pad10)") (class "Default")
      (node (ref "IC12") (pin "10") (pinfunction "~{ALERT}_10") (pintype "open_collector"))
    )
    (net (code "96") (name "unconnected-(IC13A-SD-Pad5)") (class "Default")
      (node (ref "IC13") (pin "5") (pinfunction "SD_5") (pintype "passive"))
    )
    (net (code "97") (name "unconnected-(IC14A-SD-Pad5)") (class "Default")
      (node (ref "IC14") (pin "5") (pinfunction "SD_5") (pintype "passive"))
    )
    (net (code "98") (name "unconnected-(IC15A-SD-Pad5)") (class "Default")
      (node (ref "IC15") (pin "5") (pinfunction "SD_5") (pintype "passive"))
    )
    (net (code "99") (name "unconnected-(J1-SBU1-PadA8)") (class "Default")
      (node (ref "J1") (pin "A8") (pinfunction "SBU1_A8") (pintype "bidirectional"))
    )
    (net (code "100") (name "unconnected-(J1-SBU2-PadB8)") (class "Default")
      (node (ref "J1") (pin "B8") (pinfunction "SBU2_B8") (pintype "bidirectional"))
    )
    (net (code "101") (name "unconnected-(J2-Pad6)") (class "Default")
      (node (ref "J2") (pin "6") (pinfunction "6_6") (pintype "passive"))
    )
    (net (code "102") (name "unconnected-(J2-Pad7)") (class "Default")
      (node (ref "J2") (pin "7") (pinfunction "7_7") (pintype "passive"))
    )
    (net (code "103") (name "unconnected-(J2-Pad8)") (class "Default")
      (node (ref "J2") (pin "8") (pinfunction "8_8") (pintype "passive"))
    )
    (net (code "104") (name "unconnected-(J2-Pad9)") (class "Default")
      (node (ref "J2") (pin "9") (pinfunction "9_9") (pintype "passive"))
    )
    (net (code "105") (name "~{MUX_EN}") (class "Default")
      (node (ref "IC10") (pin "28") (pinfunction "PB5_28") (pintype "bidirectional"))
      (node (ref "IC9") (pin "6") (pinfunction "~{EN}_6") (pintype "bidirectional"))
      (node (ref "R2") (pin "1") (pinfunction "1_1") (pintype "passive"))
    )
    (net (code "106") (name "~{NRST}") (class "Default")
      (node (ref "IC10") (pin "4") (pinfunction "~{NRST}_4") (pintype "bidirectional"))
      (node (ref "J2") (pin "10") (pinfunction "10_10") (pintype "passive"))
    )
    (net (code "107") (name "~{OUTPUT_ENABLE}") (class "Default")
      (node (ref "IC10") (pin "18") (pinfunction "PA8_18") (pintype "bidirectional"))
      (node (ref "IC6") (pin "5") (pinfunction "SD_5") (pintype "passive"))
      (node (ref "R45") (pin "1") (pinfunction "1_1") (pintype "passive"))
    )
  )
)
